# Index_Registers_-_1_0.net
KiCad netlist of a schematic drawn in EAGLE
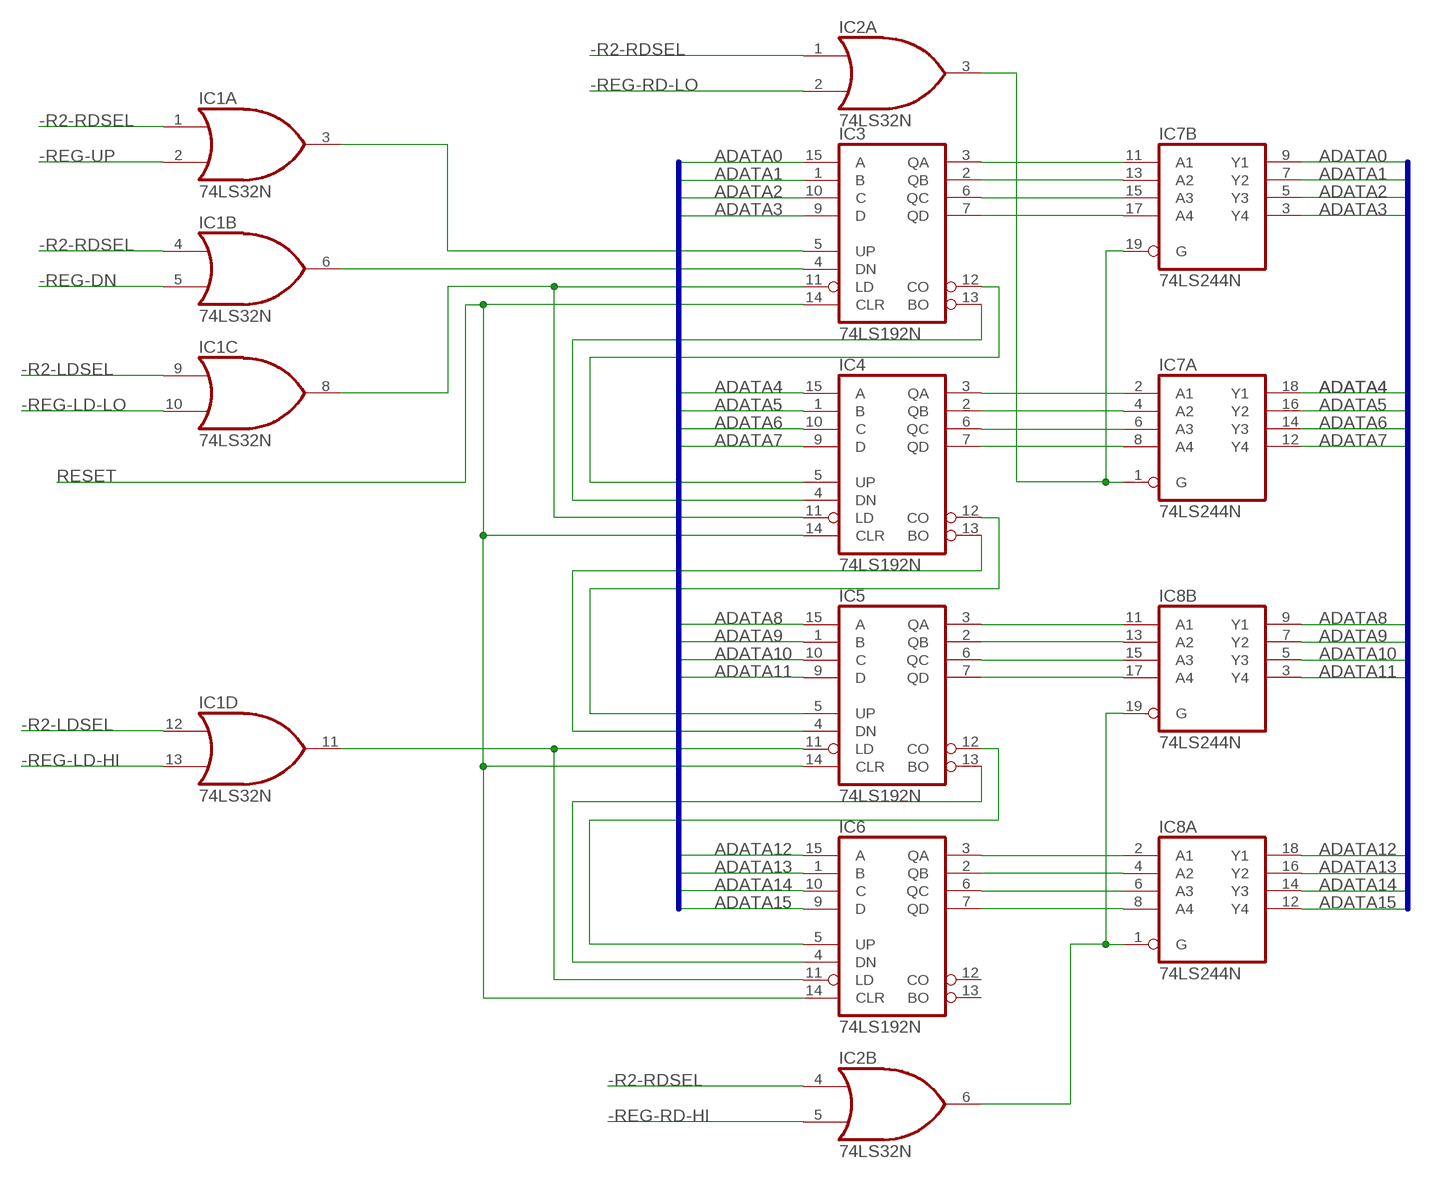
[diagram p0: schematic, sheet 1]
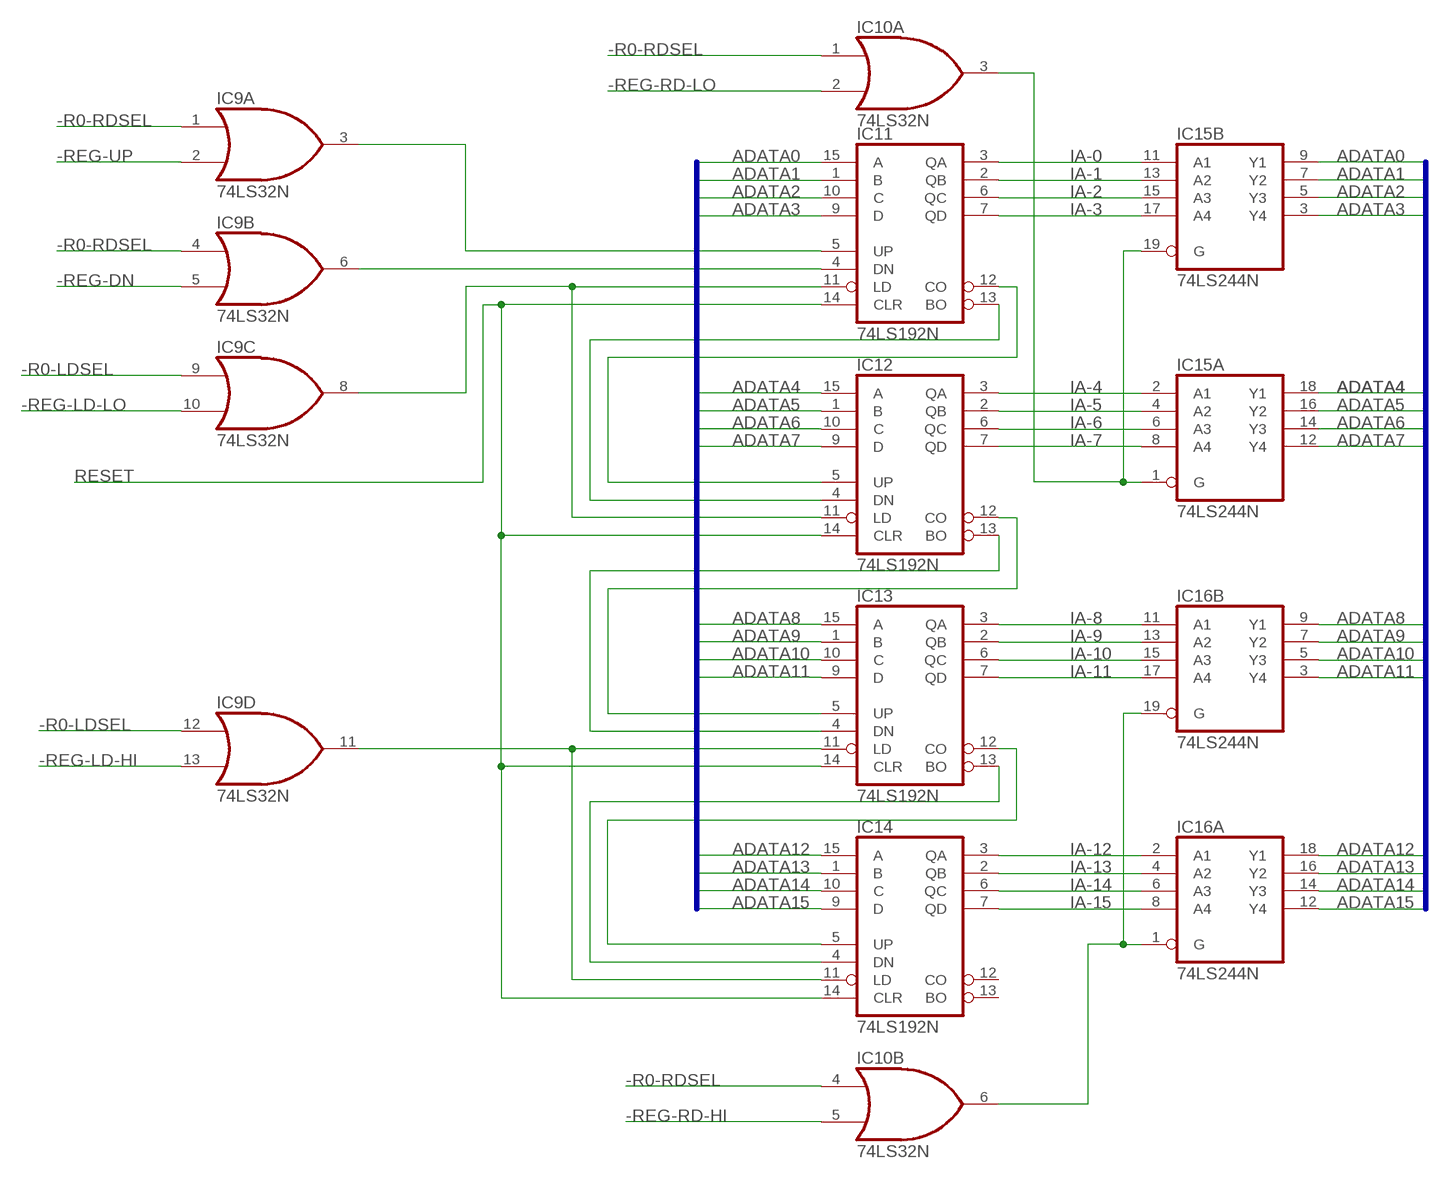
[diagram p1: schematic, sheet 2]
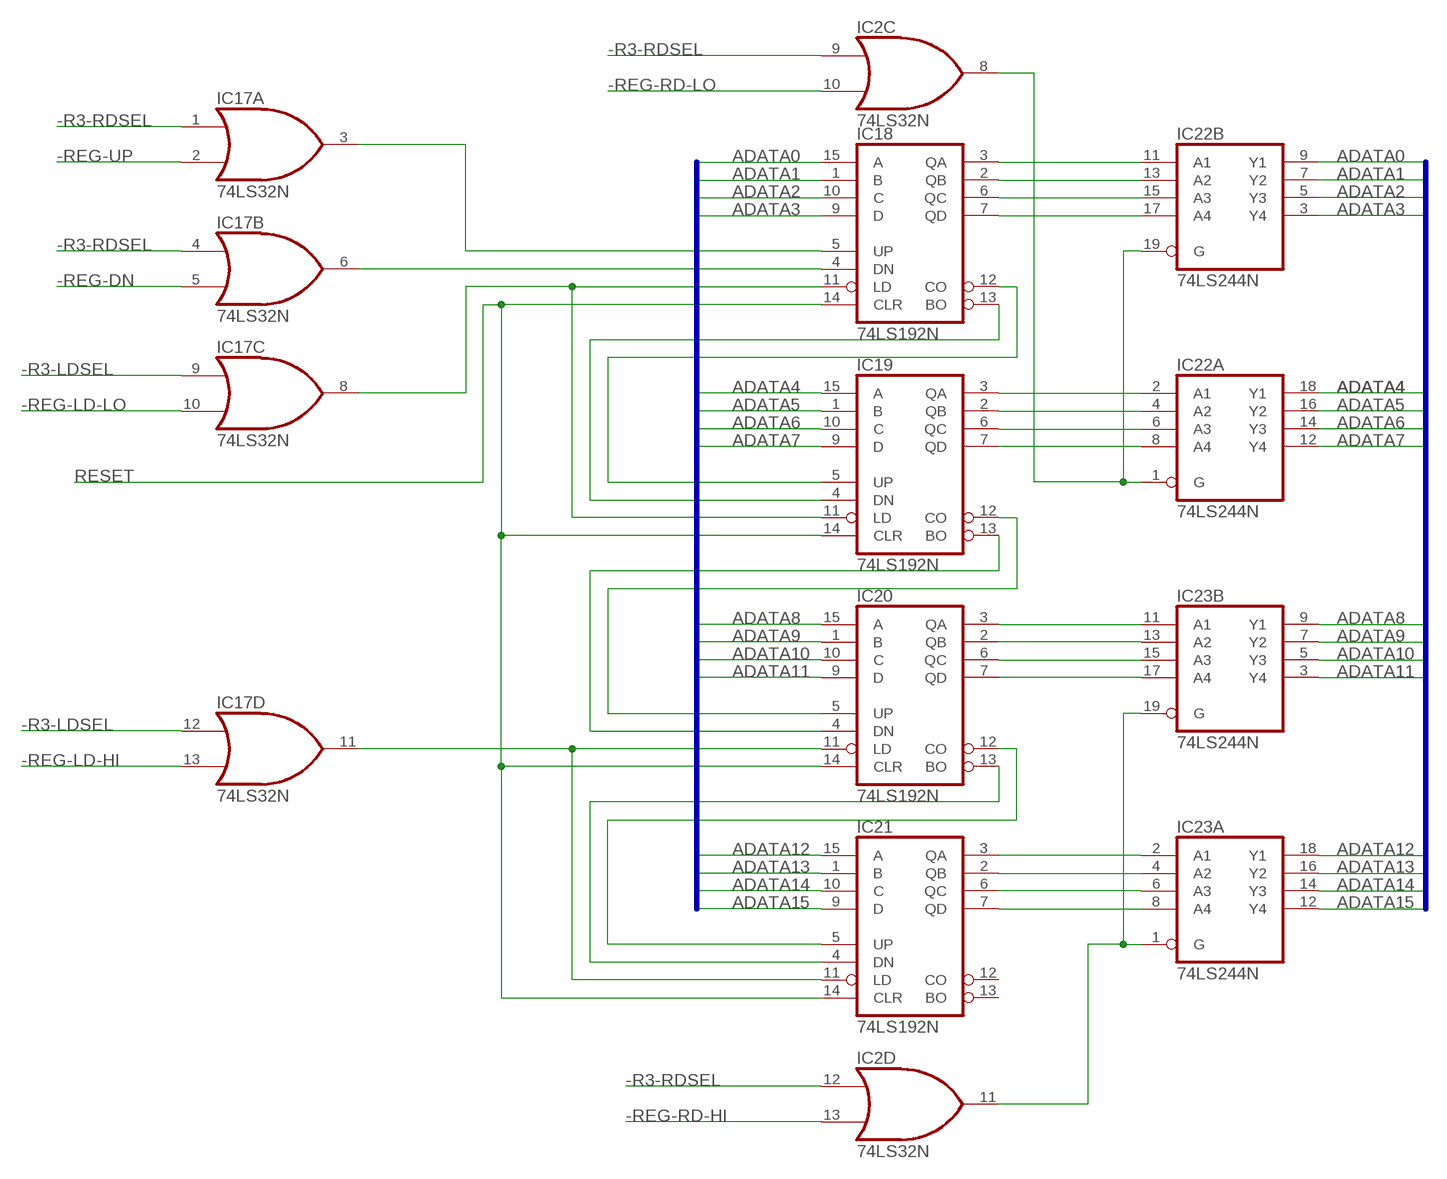
[diagram p2: schematic, sheet 3]
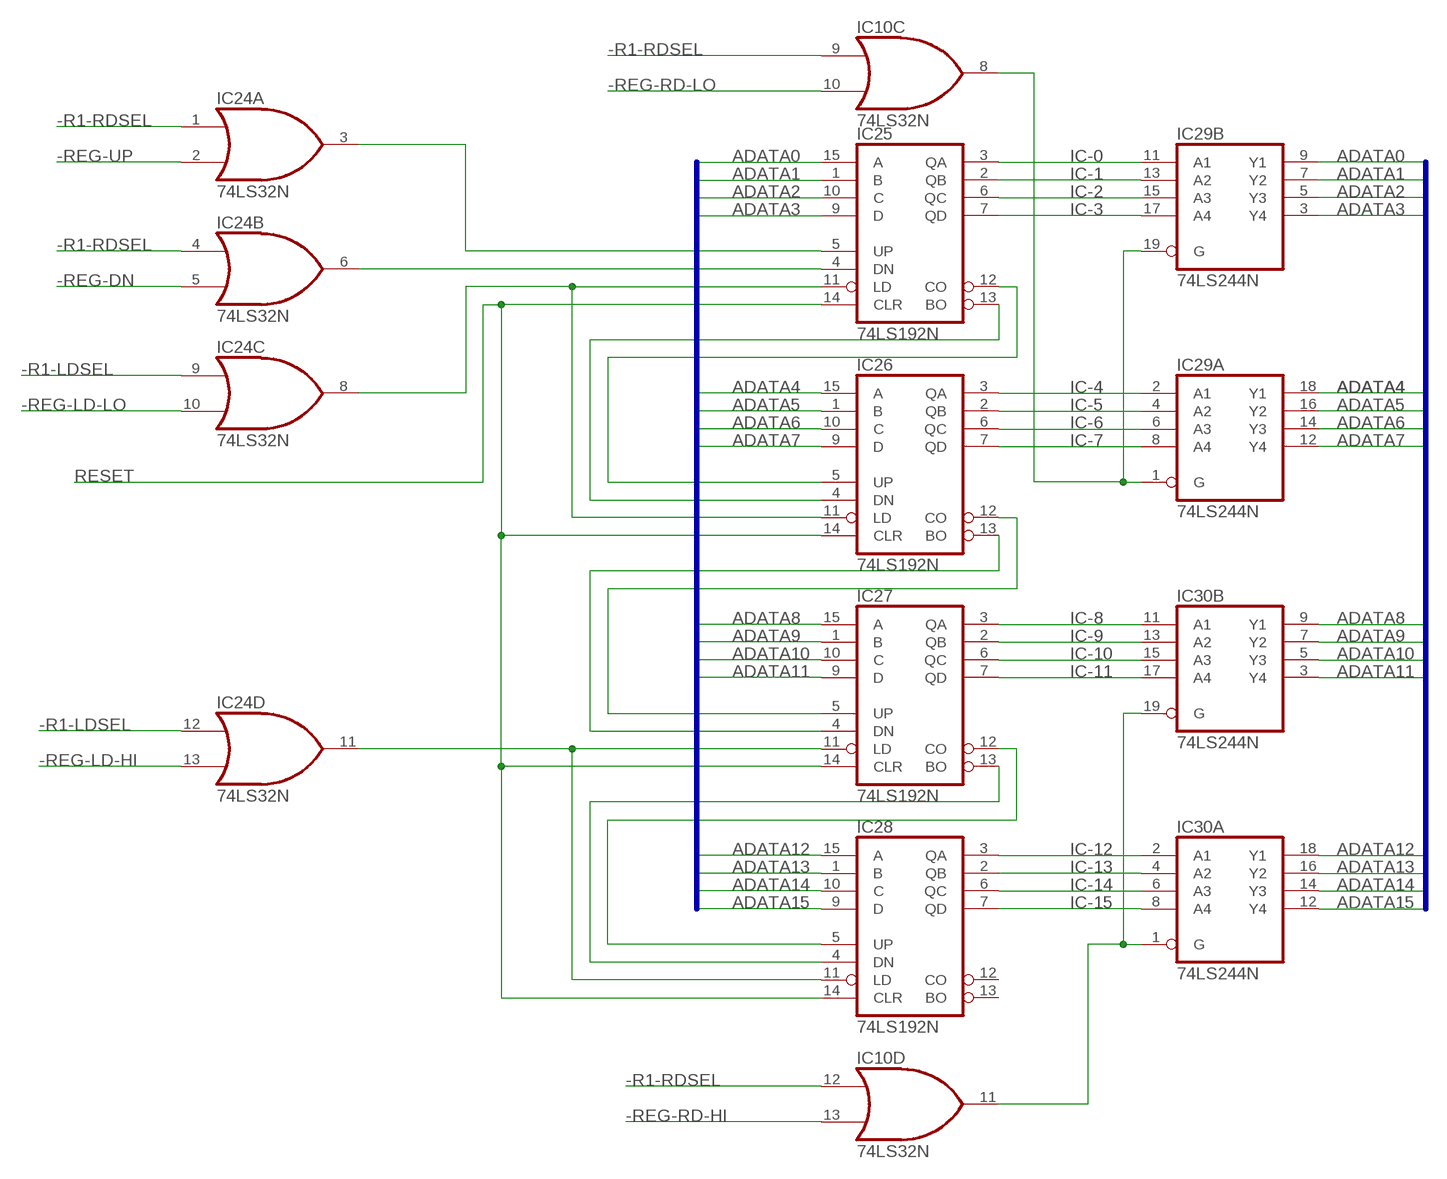
[diagram p3: schematic, sheet 4]
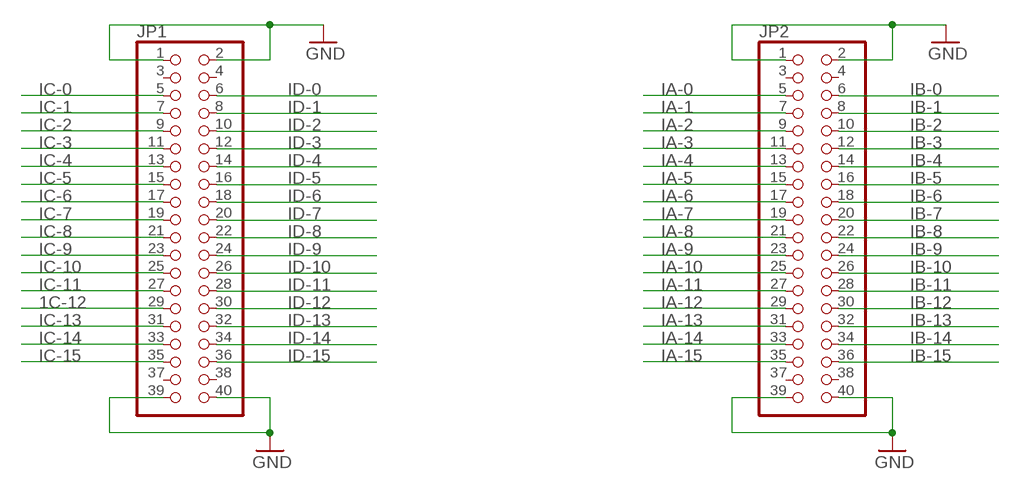
[diagram p4: schematic, sheet 5]
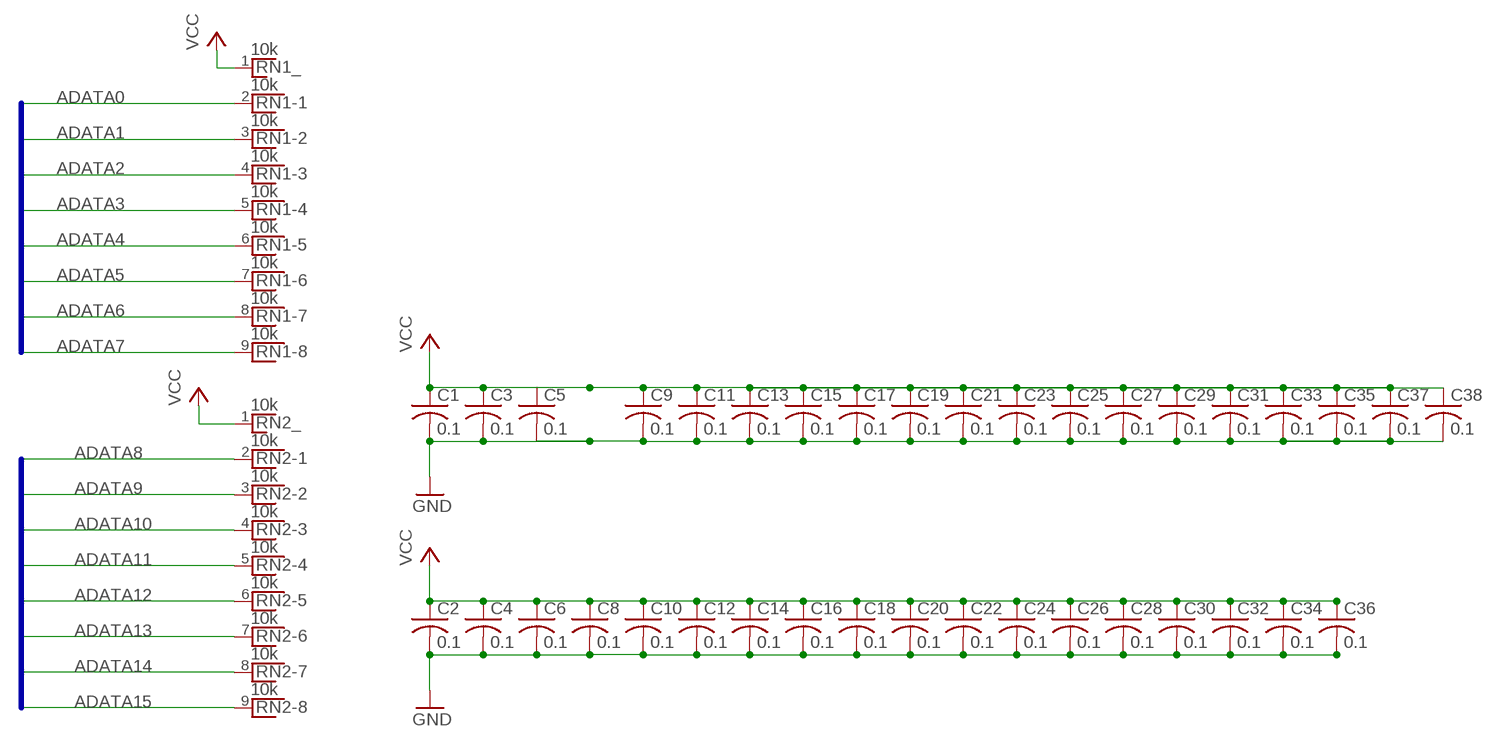
[diagram p5: schematic, sheet 6]
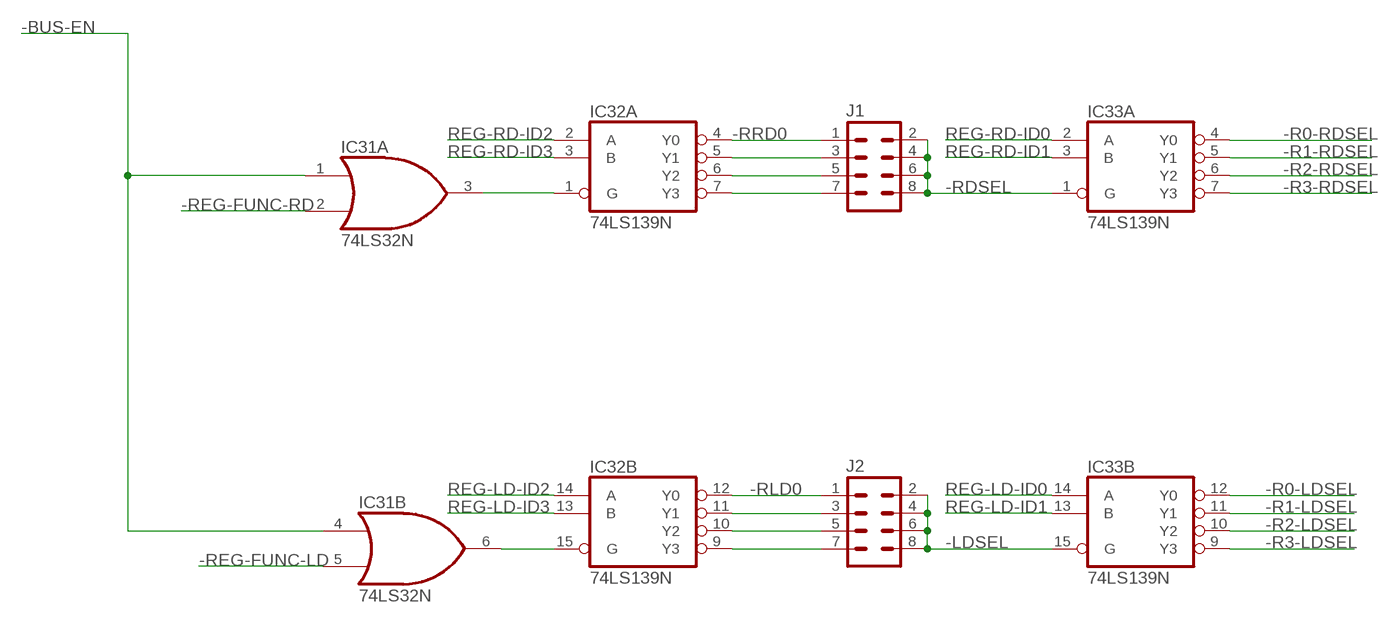
[diagram p6: schematic, sheet 7]
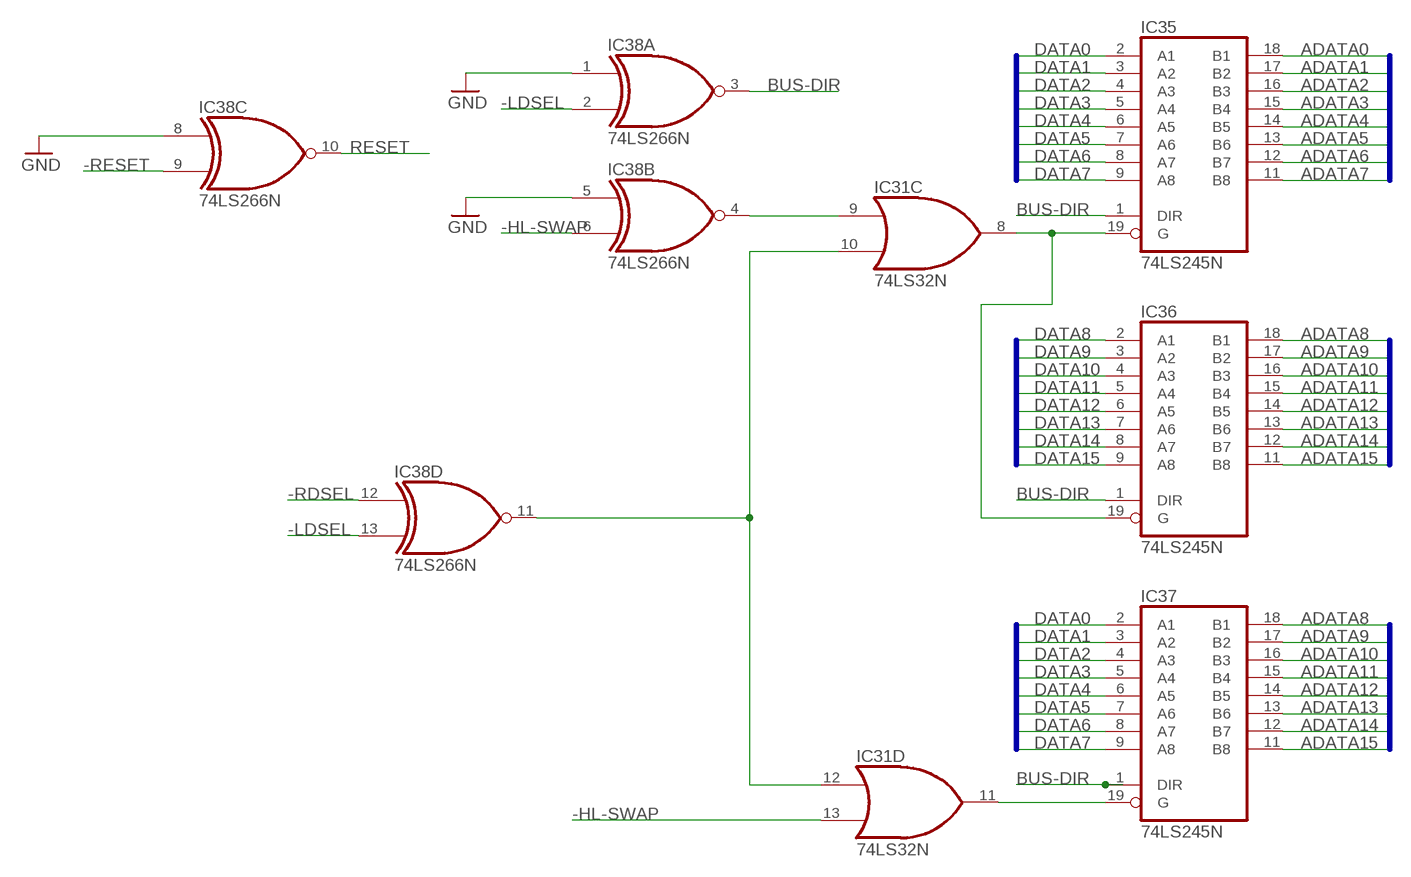
[diagram p7: schematic, sheet 8]
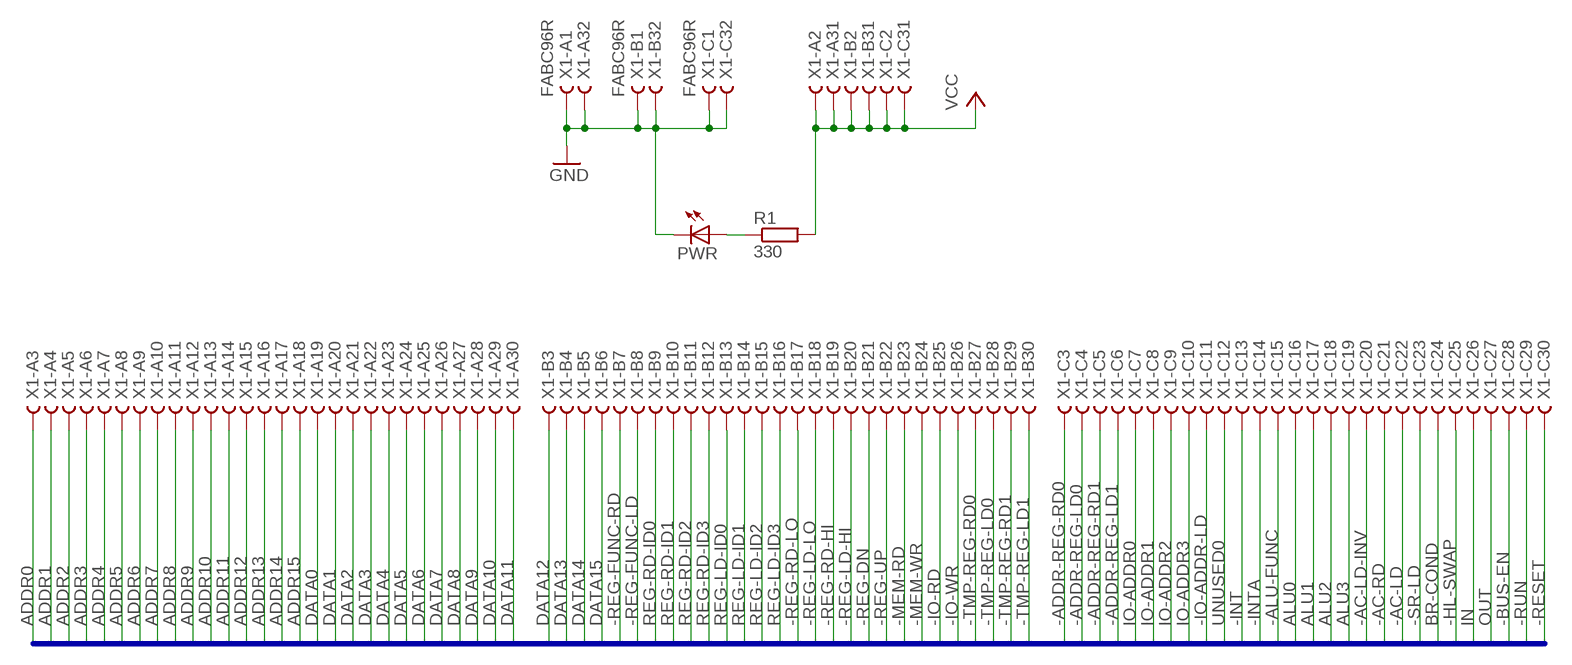
[diagram p8: schematic, sheet 9]

(export (version "E")
  (design (tool "Eeschema 10.0.6"))
  (components
    (comp (ref "IC31")
      (value "74LS32N")
      (footprint "eagle-import:DIL14")
      (libsource (lib "eagle-import") (part "7432NLS"))
    )
    (comp (ref "IC32")
      (value "74LS139N")
      (footprint "eagle-import:DIL16")
      (libsource (lib "eagle-import") (part "74139NLS"))
    )
    (comp (ref "IC33")
      (value "74LS139N")
      (footprint "eagle-import:DIL16")
      (libsource (lib "eagle-import") (part "74139NLS"))
    )
    (comp (ref "J1")
      (value "M04X2")
      (footprint "eagle-import:2X4")
      (libsource (lib "eagle-import") (part "M04X2"))
    )
    (comp (ref "J2")
      (value "M04X2")
      (footprint "eagle-import:2X4")
      (libsource (lib "eagle-import") (part "M04X2"))
    )
    (comp (ref "C1")
      (value "0.1")
      (footprint "eagle-import:C025-040X050")
      (libsource (lib "eagle-import") (part "C-US025-040X050"))
    )
    (comp (ref "C2")
      (value "0.1")
      (footprint "eagle-import:C025-040X050")
      (libsource (lib "eagle-import") (part "C-US025-040X050"))
    )
    (comp (ref "C3")
      (value "0.1")
      (footprint "eagle-import:C025-040X050")
      (libsource (lib "eagle-import") (part "C-US025-040X050"))
    )
    (comp (ref "C4")
      (value "0.1")
      (footprint "eagle-import:C025-040X050")
      (libsource (lib "eagle-import") (part "C-US025-040X050"))
    )
    (comp (ref "C5")
      (value "0.1")
      (footprint "eagle-import:C025-040X050")
      (libsource (lib "eagle-import") (part "C-US025-040X050"))
    )
    (comp (ref "C6")
      (value "0.1")
      (footprint "eagle-import:C025-040X050")
      (libsource (lib "eagle-import") (part "C-US025-040X050"))
    )
    (comp (ref "C8")
      (value "0.1")
      (footprint "eagle-import:C025-040X050")
      (libsource (lib "eagle-import") (part "C-US025-040X050"))
    )
    (comp (ref "C9")
      (value "0.1")
      (footprint "eagle-import:C025-040X050")
      (libsource (lib "eagle-import") (part "C-US025-040X050"))
    )
    (comp (ref "C10")
      (value "0.1")
      (footprint "eagle-import:C025-040X050")
      (libsource (lib "eagle-import") (part "C-US025-040X050"))
    )
    (comp (ref "C11")
      (value "0.1")
      (footprint "eagle-import:C025-040X050")
      (libsource (lib "eagle-import") (part "C-US025-040X050"))
    )
    (comp (ref "C12")
      (value "0.1")
      (footprint "eagle-import:C025-040X050")
      (libsource (lib "eagle-import") (part "C-US025-040X050"))
    )
    (comp (ref "C13")
      (value "0.1")
      (footprint "eagle-import:C025-040X050")
      (libsource (lib "eagle-import") (part "C-US025-040X050"))
    )
    (comp (ref "C14")
      (value "0.1")
      (footprint "eagle-import:C025-040X050")
      (libsource (lib "eagle-import") (part "C-US025-040X050"))
    )
    (comp (ref "C15")
      (value "0.1")
      (footprint "eagle-import:C025-040X050")
      (libsource (lib "eagle-import") (part "C-US025-040X050"))
    )
    (comp (ref "C16")
      (value "0.1")
      (footprint "eagle-import:C025-040X050")
      (libsource (lib "eagle-import") (part "C-US025-040X050"))
    )
    (comp (ref "C17")
      (value "0.1")
      (footprint "eagle-import:C025-040X050")
      (libsource (lib "eagle-import") (part "C-US025-040X050"))
    )
    (comp (ref "C18")
      (value "0.1")
      (footprint "eagle-import:C025-040X050")
      (libsource (lib "eagle-import") (part "C-US025-040X050"))
    )
    (comp (ref "C19")
      (value "0.1")
      (footprint "eagle-import:C025-040X050")
      (libsource (lib "eagle-import") (part "C-US025-040X050"))
    )
    (comp (ref "C20")
      (value "0.1")
      (footprint "eagle-import:C025-040X050")
      (libsource (lib "eagle-import") (part "C-US025-040X050"))
    )
    (comp (ref "C21")
      (value "0.1")
      (footprint "eagle-import:C025-040X050")
      (libsource (lib "eagle-import") (part "C-US025-040X050"))
    )
    (comp (ref "C22")
      (value "0.1")
      (footprint "eagle-import:C025-040X050")
      (libsource (lib "eagle-import") (part "C-US025-040X050"))
    )
    (comp (ref "C23")
      (value "0.1")
      (footprint "eagle-import:C025-040X050")
      (libsource (lib "eagle-import") (part "C-US025-040X050"))
    )
    (comp (ref "C24")
      (value "0.1")
      (footprint "eagle-import:C025-040X050")
      (libsource (lib "eagle-import") (part "C-US025-040X050"))
    )
    (comp (ref "C25")
      (value "0.1")
      (footprint "eagle-import:C025-040X050")
      (libsource (lib "eagle-import") (part "C-US025-040X050"))
    )
    (comp (ref "C26")
      (value "0.1")
      (footprint "eagle-import:C025-040X050")
      (libsource (lib "eagle-import") (part "C-US025-040X050"))
    )
    (comp (ref "C27")
      (value "0.1")
      (footprint "eagle-import:C025-040X050")
      (libsource (lib "eagle-import") (part "C-US025-040X050"))
    )
    (comp (ref "C28")
      (value "0.1")
      (footprint "eagle-import:C025-040X050")
      (libsource (lib "eagle-import") (part "C-US025-040X050"))
    )
    (comp (ref "C29")
      (value "0.1")
      (footprint "eagle-import:C025-040X050")
      (libsource (lib "eagle-import") (part "C-US025-040X050"))
    )
    (comp (ref "C30")
      (value "0.1")
      (footprint "eagle-import:C025-040X050")
      (libsource (lib "eagle-import") (part "C-US025-040X050"))
    )
    (comp (ref "C31")
      (value "0.1")
      (footprint "eagle-import:C025-040X050")
      (libsource (lib "eagle-import") (part "C-US025-040X050"))
    )
    (comp (ref "C32")
      (value "0.1")
      (footprint "eagle-import:C025-040X050")
      (libsource (lib "eagle-import") (part "C-US025-040X050"))
    )
    (comp (ref "C33")
      (value "0.1")
      (footprint "eagle-import:C025-040X050")
      (libsource (lib "eagle-import") (part "C-US025-040X050"))
    )
    (comp (ref "C34")
      (value "0.1")
      (footprint "eagle-import:C025-040X050")
      (libsource (lib "eagle-import") (part "C-US025-040X050"))
    )
    (comp (ref "C35")
      (value "0.1")
      (footprint "eagle-import:C025-040X050")
      (libsource (lib "eagle-import") (part "C-US025-040X050"))
    )
    (comp (ref "C36")
      (value "0.1")
      (footprint "eagle-import:C025-040X050")
      (libsource (lib "eagle-import") (part "C-US025-040X050"))
    )
    (comp (ref "C37")
      (value "0.1")
      (footprint "eagle-import:C025-040X050")
      (libsource (lib "eagle-import") (part "C-US025-040X050"))
    )
    (comp (ref "C38")
      (value "0.1")
      (footprint "eagle-import:C025-040X050")
      (libsource (lib "eagle-import") (part "C-US025-040X050"))
    )
    (comp (ref "RN1")
      (value "10k")
      (footprint "eagle-import:RN-9")
      (libsource (lib "eagle-import") (part "RNX8"))
    )
    (comp (ref "RN2")
      (value "10k")
      (footprint "eagle-import:RN-9")
      (libsource (lib "eagle-import") (part "RNX8"))
    )
    (comp (ref "IC1")
      (value "74LS32N")
      (footprint "eagle-import:DIL14")
      (libsource (lib "eagle-import") (part "7432NLS"))
    )
    (comp (ref "IC2")
      (value "74LS32N")
      (footprint "eagle-import:DIL14")
      (libsource (lib "eagle-import") (part "7432NLS"))
    )
    (comp (ref "IC3")
      (value "74LS192N")
      (footprint "eagle-import:DIL16")
      (libsource (lib "eagle-import") (part "74192NLS"))
    )
    (comp (ref "IC4")
      (value "74LS192N")
      (footprint "eagle-import:DIL16")
      (libsource (lib "eagle-import") (part "74192NLS"))
    )
    (comp (ref "IC5")
      (value "74LS192N")
      (footprint "eagle-import:DIL16")
      (libsource (lib "eagle-import") (part "74192NLS"))
    )
    (comp (ref "IC6")
      (value "74LS192N")
      (footprint "eagle-import:DIL16")
      (libsource (lib "eagle-import") (part "74192NLS"))
    )
    (comp (ref "IC7")
      (value "74LS244N")
      (footprint "eagle-import:DIL20")
      (libsource (lib "eagle-import") (part "74xx-us_74244NLS"))
    )
    (comp (ref "IC8")
      (value "74LS244N")
      (footprint "eagle-import:DIL20")
      (libsource (lib "eagle-import") (part "74xx-us_74244NLS"))
    )
    (comp (ref "IC17")
      (value "74LS32N")
      (footprint "eagle-import:DIL14")
      (libsource (lib "eagle-import") (part "7432NLS"))
    )
    (comp (ref "IC18")
      (value "74LS192N")
      (footprint "eagle-import:DIL16")
      (libsource (lib "eagle-import") (part "74192NLS"))
    )
    (comp (ref "IC19")
      (value "74LS192N")
      (footprint "eagle-import:DIL16")
      (libsource (lib "eagle-import") (part "74192NLS"))
    )
    (comp (ref "IC20")
      (value "74LS192N")
      (footprint "eagle-import:DIL16")
      (libsource (lib "eagle-import") (part "74192NLS"))
    )
    (comp (ref "IC21")
      (value "74LS192N")
      (footprint "eagle-import:DIL16")
      (libsource (lib "eagle-import") (part "74192NLS"))
    )
    (comp (ref "IC22")
      (value "74LS244N")
      (footprint "eagle-import:DIL20")
      (libsource (lib "eagle-import") (part "74xx-us_74244NLS"))
    )
    (comp (ref "IC23")
      (value "74LS244N")
      (footprint "eagle-import:DIL20")
      (libsource (lib "eagle-import") (part "74xx-us_74244NLS"))
    )
    (comp (ref "IC10")
      (value "74LS32N")
      (footprint "eagle-import:DIL14")
      (libsource (lib "eagle-import") (part "7432NLS"))
    )
    (comp (ref "IC24")
      (value "74LS32N")
      (footprint "eagle-import:DIL14")
      (libsource (lib "eagle-import") (part "7432NLS"))
    )
    (comp (ref "IC25")
      (value "74LS192N")
      (footprint "eagle-import:DIL16")
      (libsource (lib "eagle-import") (part "74192NLS"))
    )
    (comp (ref "IC26")
      (value "74LS192N")
      (footprint "eagle-import:DIL16")
      (libsource (lib "eagle-import") (part "74192NLS"))
    )
    (comp (ref "IC27")
      (value "74LS192N")
      (footprint "eagle-import:DIL16")
      (libsource (lib "eagle-import") (part "74192NLS"))
    )
    (comp (ref "IC28")
      (value "74LS192N")
      (footprint "eagle-import:DIL16")
      (libsource (lib "eagle-import") (part "74192NLS"))
    )
    (comp (ref "IC29")
      (value "74LS244N")
      (footprint "eagle-import:DIL20")
      (libsource (lib "eagle-import") (part "74xx-us_74244NLS"))
    )
    (comp (ref "IC30")
      (value "74LS244N")
      (footprint "eagle-import:DIL20")
      (libsource (lib "eagle-import") (part "74xx-us_74244NLS"))
    )
    (comp (ref "PWR")
      (value "LED5MM")
      (footprint "eagle-import:LED5MM")
      (libsource (lib "eagle-import") (part "LED5MM"))
    )
    (comp (ref "R1")
      (value "330")
      (footprint "eagle-import:0207_10")
      (libsource (lib "eagle-import") (part "R0207/10"))
    )
    (comp (ref "X1")
      (value "FABC96R")
      (footprint "eagle-import:FABC96R")
      (libsource (lib "eagle-import") (part "FABC96R"))
    )
    (comp (ref "JP1")
      (value "PINHD-2X20")
      (footprint "eagle-import:2X20")
      (libsource (lib "eagle-import") (part "PINHD-2X20"))
    )
    (comp (ref "JP2")
      (value "PINHD-2X20")
      (footprint "eagle-import:2X20")
      (libsource (lib "eagle-import") (part "PINHD-2X20"))
    )
    (comp (ref "IC9")
      (value "74LS32N")
      (footprint "eagle-import:DIL14")
      (libsource (lib "eagle-import") (part "7432NLS"))
    )
    (comp (ref "IC11")
      (value "74LS192N")
      (footprint "eagle-import:DIL16")
      (libsource (lib "eagle-import") (part "74192NLS"))
    )
    (comp (ref "IC12")
      (value "74LS192N")
      (footprint "eagle-import:DIL16")
      (libsource (lib "eagle-import") (part "74192NLS"))
    )
    (comp (ref "IC13")
      (value "74LS192N")
      (footprint "eagle-import:DIL16")
      (libsource (lib "eagle-import") (part "74192NLS"))
    )
    (comp (ref "IC14")
      (value "74LS192N")
      (footprint "eagle-import:DIL16")
      (libsource (lib "eagle-import") (part "74192NLS"))
    )
    (comp (ref "IC15")
      (value "74LS244N")
      (footprint "eagle-import:DIL20")
      (libsource (lib "eagle-import") (part "74xx-us_74244NLS"))
    )
    (comp (ref "IC16")
      (value "74LS244N")
      (footprint "eagle-import:DIL20")
      (libsource (lib "eagle-import") (part "74xx-us_74244NLS"))
    )
    (comp (ref "IC35")
      (value "74LS245N")
      (footprint "eagle-import:DIL20")
      (libsource (lib "eagle-import") (part "74245NLS"))
    )
    (comp (ref "IC36")
      (value "74LS245N")
      (footprint "eagle-import:DIL20")
      (libsource (lib "eagle-import") (part "74245NLS"))
    )
    (comp (ref "IC37")
      (value "74LS245N")
      (footprint "eagle-import:DIL20")
      (libsource (lib "eagle-import") (part "74245NLS"))
    )
    (comp (ref "IC38")
      (value "74LS266N")
      (footprint "eagle-import:DIL14")
      (libsource (lib "eagle-import") (part "74266NLS"))
    )
  )
  (nets
    (net (code "1") (name "-AC-LD") (class "Default")
      (node (ref "X1") (pin "C22") (pinfunction "B_C22") (pintype "passive"))
    )
    (net (code "2") (name "-AC-LD-INV") (class "Default")
      (node (ref "X1") (pin "C20") (pinfunction "B_C20") (pintype "passive"))
    )
    (net (code "3") (name "-AC-RD") (class "Default")
      (node (ref "X1") (pin "C21") (pinfunction "B_C21") (pintype "passive"))
    )
    (net (code "4") (name "-ADDR-REG-LD0") (class "Default")
      (node (ref "X1") (pin "C4") (pinfunction "B_C4") (pintype "passive"))
    )
    (net (code "5") (name "-ADDR-REG-LD1") (class "Default")
      (node (ref "X1") (pin "C6") (pinfunction "B_C6") (pintype "passive"))
    )
    (net (code "6") (name "-ADDR-REG-RD0") (class "Default")
      (node (ref "X1") (pin "C3") (pinfunction "B_C3") (pintype "passive"))
    )
    (net (code "7") (name "-ADDR-REG-RD1") (class "Default")
      (node (ref "X1") (pin "C5") (pinfunction "B_C5") (pintype "passive"))
    )
    (net (code "8") (name "-ALU-FUNC") (class "Default")
      (node (ref "X1") (pin "C15") (pinfunction "B_C15") (pintype "passive"))
    )
    (net (code "9") (name "-BUS-EN") (class "Default")
      (node (ref "IC31") (pin "1") (pinfunction "I0_1") (pintype "input"))
      (node (ref "IC31") (pin "4") (pinfunction "I0_4") (pintype "input"))
      (node (ref "X1") (pin "C28") (pinfunction "B_C28") (pintype "passive"))
    )
    (net (code "10") (name "-HL-SWAP") (class "Default")
      (node (ref "IC31") (pin "13") (pinfunction "I1_13") (pintype "input"))
      (node (ref "IC38") (pin "6") (pinfunction "I1_6") (pintype "input"))
      (node (ref "X1") (pin "C25") (pinfunction "B_C25") (pintype "passive"))
    )
    (net (code "11") (name "-INT") (class "Default")
      (node (ref "X1") (pin "C13") (pinfunction "B_C13") (pintype "passive"))
    )
    (net (code "12") (name "-INTA") (class "Default")
      (node (ref "X1") (pin "C14") (pinfunction "B_C14") (pintype "passive"))
    )
    (net (code "13") (name "-IO-ADDR-LD") (class "Default")
      (node (ref "X1") (pin "C11") (pinfunction "B_C11") (pintype "passive"))
    )
    (net (code "14") (name "-IO-RD") (class "Default")
      (node (ref "X1") (pin "B25") (pinfunction "B_B25") (pintype "passive"))
    )
    (net (code "15") (name "-IO-WR") (class "Default")
      (node (ref "X1") (pin "B26") (pinfunction "B_B26") (pintype "passive"))
    )
    (net (code "16") (name "-LDSEL") (class "Default")
      (node (ref "IC33") (pin "15") (pinfunction "G_15") (pintype "input"))
      (node (ref "IC38") (pin "13") (pinfunction "I1_13") (pintype "input"))
      (node (ref "IC38") (pin "2") (pinfunction "I1_2") (pintype "input"))
      (node (ref "J2") (pin "2") (pinfunction "2_2") (pintype "passive"))
      (node (ref "J2") (pin "4") (pinfunction "4_4") (pintype "passive"))
      (node (ref "J2") (pin "6") (pinfunction "6_6") (pintype "passive"))
      (node (ref "J2") (pin "8") (pinfunction "8_8") (pintype "passive"))
    )
    (net (code "17") (name "-MEM-RD") (class "Default")
      (node (ref "X1") (pin "B23") (pinfunction "B_B23") (pintype "passive"))
    )
    (net (code "18") (name "-MEM-WR") (class "Default")
      (node (ref "X1") (pin "B24") (pinfunction "B_B24") (pintype "passive"))
    )
    (net (code "19") (name "-R0-LDSEL") (class "Default")
      (node (ref "IC33") (pin "12") (pinfunction "Y0_12") (pintype "output"))
      (node (ref "IC9") (pin "12") (pinfunction "I0_12") (pintype "input"))
      (node (ref "IC9") (pin "9") (pinfunction "I0_9") (pintype "input"))
    )
    (net (code "20") (name "-R0-RDSEL") (class "Default")
      (node (ref "IC10") (pin "1") (pinfunction "I0_1") (pintype "input"))
      (node (ref "IC10") (pin "4") (pinfunction "I0_4") (pintype "input"))
      (node (ref "IC33") (pin "4") (pinfunction "Y0_4") (pintype "output"))
      (node (ref "IC9") (pin "1") (pinfunction "I0_1") (pintype "input"))
      (node (ref "IC9") (pin "4") (pinfunction "I0_4") (pintype "input"))
    )
    (net (code "21") (name "-R1-LDSEL") (class "Default")
      (node (ref "IC24") (pin "12") (pinfunction "I0_12") (pintype "input"))
      (node (ref "IC24") (pin "9") (pinfunction "I0_9") (pintype "input"))
      (node (ref "IC33") (pin "11") (pinfunction "Y1_11") (pintype "output"))
    )
    (net (code "22") (name "-R1-RDSEL") (class "Default")
      (node (ref "IC10") (pin "12") (pinfunction "I0_12") (pintype "input"))
      (node (ref "IC10") (pin "9") (pinfunction "I0_9") (pintype "input"))
      (node (ref "IC24") (pin "1") (pinfunction "I0_1") (pintype "input"))
      (node (ref "IC24") (pin "4") (pinfunction "I0_4") (pintype "input"))
      (node (ref "IC33") (pin "5") (pinfunction "Y1_5") (pintype "output"))
    )
    (net (code "23") (name "-R2-LDSEL") (class "Default")
      (node (ref "IC1") (pin "12") (pinfunction "I0_12") (pintype "input"))
      (node (ref "IC1") (pin "9") (pinfunction "I0_9") (pintype "input"))
      (node (ref "IC33") (pin "10") (pinfunction "Y2_10") (pintype "output"))
    )
    (net (code "24") (name "-R2-RDSEL") (class "Default")
      (node (ref "IC1") (pin "1") (pinfunction "I0_1") (pintype "input"))
      (node (ref "IC1") (pin "4") (pinfunction "I0_4") (pintype "input"))
      (node (ref "IC2") (pin "1") (pinfunction "I0_1") (pintype "input"))
      (node (ref "IC2") (pin "4") (pinfunction "I0_4") (pintype "input"))
      (node (ref "IC33") (pin "6") (pinfunction "Y2_6") (pintype "output"))
    )
    (net (code "25") (name "-R3-LDSEL") (class "Default")
      (node (ref "IC17") (pin "12") (pinfunction "I0_12") (pintype "input"))
      (node (ref "IC17") (pin "9") (pinfunction "I0_9") (pintype "input"))
      (node (ref "IC33") (pin "9") (pinfunction "Y3_9") (pintype "output"))
    )
    (net (code "26") (name "-R3-RDSEL") (class "Default")
      (node (ref "IC17") (pin "1") (pinfunction "I0_1") (pintype "input"))
      (node (ref "IC17") (pin "4") (pinfunction "I0_4") (pintype "input"))
      (node (ref "IC2") (pin "12") (pinfunction "I0_12") (pintype "input"))
      (node (ref "IC2") (pin "9") (pinfunction "I0_9") (pintype "input"))
      (node (ref "IC33") (pin "7") (pinfunction "Y3_7") (pintype "output"))
    )
    (net (code "27") (name "-RDSEL") (class "Default")
      (node (ref "IC33") (pin "1") (pinfunction "G_1") (pintype "input"))
      (node (ref "IC38") (pin "12") (pinfunction "I0_12") (pintype "input"))
      (node (ref "J1") (pin "2") (pinfunction "2_2") (pintype "passive"))
      (node (ref "J1") (pin "4") (pinfunction "4_4") (pintype "passive"))
      (node (ref "J1") (pin "6") (pinfunction "6_6") (pintype "passive"))
      (node (ref "J1") (pin "8") (pinfunction "8_8") (pintype "passive"))
    )
    (net (code "28") (name "-REG-DN") (class "Default")
      (node (ref "IC1") (pin "5") (pinfunction "I1_5") (pintype "input"))
      (node (ref "IC17") (pin "5") (pinfunction "I1_5") (pintype "input"))
      (node (ref "IC24") (pin "5") (pinfunction "I1_5") (pintype "input"))
      (node (ref "IC9") (pin "5") (pinfunction "I1_5") (pintype "input"))
      (node (ref "X1") (pin "B21") (pinfunction "B_B21") (pintype "passive"))
    )
    (net (code "29") (name "-REG-FUNC-LD") (class "Default")
      (node (ref "IC31") (pin "5") (pinfunction "I1_5") (pintype "input"))
      (node (ref "X1") (pin "B8") (pinfunction "B_B8") (pintype "passive"))
    )
    (net (code "30") (name "-REG-FUNC-RD") (class "Default")
      (node (ref "IC31") (pin "2") (pinfunction "I1_2") (pintype "input"))
      (node (ref "X1") (pin "B7") (pinfunction "B_B7") (pintype "passive"))
    )
    (net (code "31") (name "-REG-LD-HI") (class "Default")
      (node (ref "IC1") (pin "13") (pinfunction "I1_13") (pintype "input"))
      (node (ref "IC17") (pin "13") (pinfunction "I1_13") (pintype "input"))
      (node (ref "IC24") (pin "13") (pinfunction "I1_13") (pintype "input"))
      (node (ref "IC9") (pin "13") (pinfunction "I1_13") (pintype "input"))
      (node (ref "X1") (pin "B20") (pinfunction "B_B20") (pintype "passive"))
    )
    (net (code "32") (name "-REG-LD-LO") (class "Default")
      (node (ref "IC1") (pin "10") (pinfunction "I1_10") (pintype "input"))
      (node (ref "IC17") (pin "10") (pinfunction "I1_10") (pintype "input"))
      (node (ref "IC24") (pin "10") (pinfunction "I1_10") (pintype "input"))
      (node (ref "IC9") (pin "10") (pinfunction "I1_10") (pintype "input"))
      (node (ref "X1") (pin "B18") (pinfunction "B_B18") (pintype "passive"))
    )
    (net (code "33") (name "-REG-RD-HI") (class "Default")
      (node (ref "IC10") (pin "13") (pinfunction "I1_13") (pintype "input"))
      (node (ref "IC10") (pin "5") (pinfunction "I1_5") (pintype "input"))
      (node (ref "IC2") (pin "13") (pinfunction "I1_13") (pintype "input"))
      (node (ref "IC2") (pin "5") (pinfunction "I1_5") (pintype "input"))
      (node (ref "X1") (pin "B19") (pinfunction "B_B19") (pintype "passive"))
    )
    (net (code "34") (name "-REG-RD-LO") (class "Default")
      (node (ref "IC10") (pin "10") (pinfunction "I1_10") (pintype "input"))
      (node (ref "IC10") (pin "2") (pinfunction "I1_2") (pintype "input"))
      (node (ref "IC2") (pin "10") (pinfunction "I1_10") (pintype "input"))
      (node (ref "IC2") (pin "2") (pinfunction "I1_2") (pintype "input"))
      (node (ref "X1") (pin "B17") (pinfunction "B_B17") (pintype "passive"))
    )
    (net (code "35") (name "-REG-UP") (class "Default")
      (node (ref "IC1") (pin "2") (pinfunction "I1_2") (pintype "input"))
      (node (ref "IC17") (pin "2") (pinfunction "I1_2") (pintype "input"))
      (node (ref "IC24") (pin "2") (pinfunction "I1_2") (pintype "input"))
      (node (ref "IC9") (pin "2") (pinfunction "I1_2") (pintype "input"))
      (node (ref "X1") (pin "B22") (pinfunction "B_B22") (pintype "passive"))
    )
    (net (code "36") (name "-RESET") (class "Default")
      (node (ref "IC38") (pin "9") (pinfunction "I1_9") (pintype "input"))
      (node (ref "X1") (pin "C30") (pinfunction "B_C30") (pintype "passive"))
    )
    (net (code "37") (name "-RLD0") (class "Default")
      (node (ref "IC32") (pin "12") (pinfunction "Y0_12") (pintype "output"))
      (node (ref "J2") (pin "1") (pinfunction "1_1") (pintype "passive"))
    )
    (net (code "38") (name "-RRD0") (class "Default")
      (node (ref "IC32") (pin "4") (pinfunction "Y0_4") (pintype "output"))
      (node (ref "J1") (pin "1") (pinfunction "1_1") (pintype "passive"))
    )
    (net (code "39") (name "-RUN") (class "Default")
      (node (ref "X1") (pin "C29") (pinfunction "B_C29") (pintype "passive"))
    )
    (net (code "40") (name "-SR-LD") (class "Default")
      (node (ref "X1") (pin "C23") (pinfunction "B_C23") (pintype "passive"))
    )
    (net (code "41") (name "-TMP-REG-LD0") (class "Default")
      (node (ref "X1") (pin "B28") (pinfunction "B_B28") (pintype "passive"))
    )
    (net (code "42") (name "-TMP-REG-LD1") (class "Default")
      (node (ref "X1") (pin "B30") (pinfunction "B_B30") (pintype "passive"))
    )
    (net (code "43") (name "-TMP-REG-RD0") (class "Default")
      (node (ref "X1") (pin "B27") (pinfunction "B_B27") (pintype "passive"))
    )
    (net (code "44") (name "-TMP-REG-RD1") (class "Default")
      (node (ref "X1") (pin "B29") (pinfunction "B_B29") (pintype "passive"))
    )
    (net (code "45") (name "1C-12") (class "Default")
      (node (ref "JP1") (pin "29") (pinfunction "29_29") (pintype "passive"))
    )
    (net (code "46") (name "ADATA0") (class "Default")
      (node (ref "IC11") (pin "15") (pinfunction "A_15") (pintype "input"))
      (node (ref "IC15") (pin "9") (pinfunction "Y1_9") (pintype "tri_state"))
      (node (ref "IC18") (pin "15") (pinfunction "A_15") (pintype "input"))
      (node (ref "IC22") (pin "9") (pinfunction "Y1_9") (pintype "tri_state"))
      (node (ref "IC25") (pin "15") (pinfunction "A_15") (pintype "input"))
      (node (ref "IC29") (pin "9") (pinfunction "Y1_9") (pintype "tri_state"))
      (node (ref "IC3") (pin "15") (pinfunction "A_15") (pintype "input"))
      (node (ref "IC35") (pin "18") (pinfunction "B1_18") (pintype "bidirectional"))
      (node (ref "IC7") (pin "9") (pinfunction "Y1_9") (pintype "tri_state"))
      (node (ref "RN1") (pin "2") (pinfunction "1_2") (pintype "passive"))
    )
    (net (code "47") (name "ADATA1") (class "Default")
      (node (ref "IC11") (pin "1") (pinfunction "B_1") (pintype "input"))
      (node (ref "IC15") (pin "7") (pinfunction "Y2_7") (pintype "tri_state"))
      (node (ref "IC18") (pin "1") (pinfunction "B_1") (pintype "input"))
      (node (ref "IC22") (pin "7") (pinfunction "Y2_7") (pintype "tri_state"))
      (node (ref "IC25") (pin "1") (pinfunction "B_1") (pintype "input"))
      (node (ref "IC29") (pin "7") (pinfunction "Y2_7") (pintype "tri_state"))
      (node (ref "IC3") (pin "1") (pinfunction "B_1") (pintype "input"))
      (node (ref "IC35") (pin "17") (pinfunction "B2_17") (pintype "bidirectional"))
      (node (ref "IC7") (pin "7") (pinfunction "Y2_7") (pintype "tri_state"))
      (node (ref "RN1") (pin "3") (pinfunction "1_3") (pintype "passive"))
    )
    (net (code "48") (name "ADATA2") (class "Default")
      (node (ref "IC11") (pin "10") (pinfunction "C_10") (pintype "input"))
      (node (ref "IC15") (pin "5") (pinfunction "Y3_5") (pintype "tri_state"))
      (node (ref "IC18") (pin "10") (pinfunction "C_10") (pintype "input"))
      (node (ref "IC22") (pin "5") (pinfunction "Y3_5") (pintype "tri_state"))
      (node (ref "IC25") (pin "10") (pinfunction "C_10") (pintype "input"))
      (node (ref "IC29") (pin "5") (pinfunction "Y3_5") (pintype "tri_state"))
      (node (ref "IC3") (pin "10") (pinfunction "C_10") (pintype "input"))
      (node (ref "IC35") (pin "16") (pinfunction "B3_16") (pintype "bidirectional"))
      (node (ref "IC7") (pin "5") (pinfunction "Y3_5") (pintype "tri_state"))
      (node (ref "RN1") (pin "4") (pinfunction "1_4") (pintype "passive"))
    )
    (net (code "49") (name "ADATA3") (class "Default")
      (node (ref "IC11") (pin "9") (pinfunction "D_9") (pintype "input"))
      (node (ref "IC15") (pin "3") (pinfunction "Y4_3") (pintype "tri_state"))
      (node (ref "IC18") (pin "9") (pinfunction "D_9") (pintype "input"))
      (node (ref "IC22") (pin "3") (pinfunction "Y4_3") (pintype "tri_state"))
      (node (ref "IC25") (pin "9") (pinfunction "D_9") (pintype "input"))
      (node (ref "IC29") (pin "3") (pinfunction "Y4_3") (pintype "tri_state"))
      (node (ref "IC3") (pin "9") (pinfunction "D_9") (pintype "input"))
      (node (ref "IC35") (pin "15") (pinfunction "B4_15") (pintype "bidirectional"))
      (node (ref "IC7") (pin "3") (pinfunction "Y4_3") (pintype "tri_state"))
      (node (ref "RN1") (pin "5") (pinfunction "1_5") (pintype "passive"))
    )
    (net (code "50") (name "ADATA4") (class "Default")
      (node (ref "IC12") (pin "15") (pinfunction "A_15") (pintype "input"))
      (node (ref "IC15") (pin "18") (pinfunction "Y1_18") (pintype "tri_state"))
      (node (ref "IC19") (pin "15") (pinfunction "A_15") (pintype "input"))
      (node (ref "IC22") (pin "18") (pinfunction "Y1_18") (pintype "tri_state"))
      (node (ref "IC26") (pin "15") (pinfunction "A_15") (pintype "input"))
      (node (ref "IC29") (pin "18") (pinfunction "Y1_18") (pintype "tri_state"))
      (node (ref "IC35") (pin "14") (pinfunction "B5_14") (pintype "bidirectional"))
      (node (ref "IC4") (pin "15") (pinfunction "A_15") (pintype "input"))
      (node (ref "IC7") (pin "18") (pinfunction "Y1_18") (pintype "tri_state"))
      (node (ref "RN1") (pin "6") (pinfunction "1_6") (pintype "passive"))
    )
    (net (code "51") (name "ADATA5") (class "Default")
      (node (ref "IC12") (pin "1") (pinfunction "B_1") (pintype "input"))
      (node (ref "IC15") (pin "16") (pinfunction "Y2_16") (pintype "tri_state"))
      (node (ref "IC19") (pin "1") (pinfunction "B_1") (pintype "input"))
      (node (ref "IC22") (pin "16") (pinfunction "Y2_16") (pintype "tri_state"))
      (node (ref "IC26") (pin "1") (pinfunction "B_1") (pintype "input"))
      (node (ref "IC29") (pin "16") (pinfunction "Y2_16") (pintype "tri_state"))
      (node (ref "IC35") (pin "13") (pinfunction "B6_13") (pintype "bidirectional"))
      (node (ref "IC4") (pin "1") (pinfunction "B_1") (pintype "input"))
      (node (ref "IC7") (pin "16") (pinfunction "Y2_16") (pintype "tri_state"))
      (node (ref "RN1") (pin "7") (pinfunction "1_7") (pintype "passive"))
    )
    (net (code "52") (name "ADATA6") (class "Default")
      (node (ref "IC12") (pin "10") (pinfunction "C_10") (pintype "input"))
      (node (ref "IC15") (pin "14") (pinfunction "Y3_14") (pintype "tri_state"))
      (node (ref "IC19") (pin "10") (pinfunction "C_10") (pintype "input"))
      (node (ref "IC22") (pin "14") (pinfunction "Y3_14") (pintype "tri_state"))
      (node (ref "IC26") (pin "10") (pinfunction "C_10") (pintype "input"))
      (node (ref "IC29") (pin "14") (pinfunction "Y3_14") (pintype "tri_state"))
      (node (ref "IC35") (pin "12") (pinfunction "B7_12") (pintype "bidirectional"))
      (node (ref "IC4") (pin "10") (pinfunction "C_10") (pintype "input"))
      (node (ref "IC7") (pin "14") (pinfunction "Y3_14") (pintype "tri_state"))
      (node (ref "RN1") (pin "8") (pinfunction "1_8") (pintype "passive"))
    )
    (net (code "53") (name "ADATA7") (class "Default")
      (node (ref "IC12") (pin "9") (pinfunction "D_9") (pintype "input"))
      (node (ref "IC15") (pin "12") (pinfunction "Y4_12") (pintype "tri_state"))
      (node (ref "IC19") (pin "9") (pinfunction "D_9") (pintype "input"))
      (node (ref "IC22") (pin "12") (pinfunction "Y4_12") (pintype "tri_state"))
      (node (ref "IC26") (pin "9") (pinfunction "D_9") (pintype "input"))
      (node (ref "IC29") (pin "12") (pinfunction "Y4_12") (pintype "tri_state"))
      (node (ref "IC35") (pin "11") (pinfunction "B8_11") (pintype "bidirectional"))
      (node (ref "IC4") (pin "9") (pinfunction "D_9") (pintype "input"))
      (node (ref "IC7") (pin "12") (pinfunction "Y4_12") (pintype "tri_state"))
      (node (ref "RN1") (pin "9") (pinfunction "1_9") (pintype "passive"))
    )
    (net (code "54") (name "ADATA8") (class "Default")
      (node (ref "IC13") (pin "15") (pinfunction "A_15") (pintype "input"))
      (node (ref "IC16") (pin "9") (pinfunction "Y1_9") (pintype "tri_state"))
      (node (ref "IC20") (pin "15") (pinfunction "A_15") (pintype "input"))
      (node (ref "IC23") (pin "9") (pinfunction "Y1_9") (pintype "tri_state"))
      (node (ref "IC27") (pin "15") (pinfunction "A_15") (pintype "input"))
      (node (ref "IC30") (pin "9") (pinfunction "Y1_9") (pintype "tri_state"))
      (node (ref "IC36") (pin "18") (pinfunction "B1_18") (pintype "bidirectional"))
      (node (ref "IC37") (pin "18") (pinfunction "B1_18") (pintype "bidirectional"))
      (node (ref "IC5") (pin "15") (pinfunction "A_15") (pintype "input"))
      (node (ref "IC8") (pin "9") (pinfunction "Y1_9") (pintype "tri_state"))
      (node (ref "RN2") (pin "2") (pinfunction "1_2") (pintype "passive"))
    )
    (net (code "55") (name "ADATA9") (class "Default")
      (node (ref "IC13") (pin "1") (pinfunction "B_1") (pintype "input"))
      (node (ref "IC16") (pin "7") (pinfunction "Y2_7") (pintype "tri_state"))
      (node (ref "IC20") (pin "1") (pinfunction "B_1") (pintype "input"))
      (node (ref "IC23") (pin "7") (pinfunction "Y2_7") (pintype "tri_state"))
      (node (ref "IC27") (pin "1") (pinfunction "B_1") (pintype "input"))
      (node (ref "IC30") (pin "7") (pinfunction "Y2_7") (pintype "tri_state"))
      (node (ref "IC36") (pin "17") (pinfunction "B2_17") (pintype "bidirectional"))
      (node (ref "IC37") (pin "17") (pinfunction "B2_17") (pintype "bidirectional"))
      (node (ref "IC5") (pin "1") (pinfunction "B_1") (pintype "input"))
      (node (ref "IC8") (pin "7") (pinfunction "Y2_7") (pintype "tri_state"))
      (node (ref "RN2") (pin "3") (pinfunction "1_3") (pintype "passive"))
    )
    (net (code "56") (name "ADATA10") (class "Default")
      (node (ref "IC13") (pin "10") (pinfunction "C_10") (pintype "input"))
      (node (ref "IC16") (pin "5") (pinfunction "Y3_5") (pintype "tri_state"))
      (node (ref "IC20") (pin "10") (pinfunction "C_10") (pintype "input"))
      (node (ref "IC23") (pin "5") (pinfunction "Y3_5") (pintype "tri_state"))
      (node (ref "IC27") (pin "10") (pinfunction "C_10") (pintype "input"))
      (node (ref "IC30") (pin "5") (pinfunction "Y3_5") (pintype "tri_state"))
      (node (ref "IC36") (pin "16") (pinfunction "B3_16") (pintype "bidirectional"))
      (node (ref "IC37") (pin "16") (pinfunction "B3_16") (pintype "bidirectional"))
      (node (ref "IC5") (pin "10") (pinfunction "C_10") (pintype "input"))
      (node (ref "IC8") (pin "5") (pinfunction "Y3_5") (pintype "tri_state"))
      (node (ref "RN2") (pin "4") (pinfunction "1_4") (pintype "passive"))
    )
    (net (code "57") (name "ADATA11") (class "Default")
      (node (ref "IC13") (pin "9") (pinfunction "D_9") (pintype "input"))
      (node (ref "IC16") (pin "3") (pinfunction "Y4_3") (pintype "tri_state"))
      (node (ref "IC20") (pin "9") (pinfunction "D_9") (pintype "input"))
      (node (ref "IC23") (pin "3") (pinfunction "Y4_3") (pintype "tri_state"))
      (node (ref "IC27") (pin "9") (pinfunction "D_9") (pintype "input"))
      (node (ref "IC30") (pin "3") (pinfunction "Y4_3") (pintype "tri_state"))
      (node (ref "IC36") (pin "15") (pinfunction "B4_15") (pintype "bidirectional"))
      (node (ref "IC37") (pin "15") (pinfunction "B4_15") (pintype "bidirectional"))
      (node (ref "IC5") (pin "9") (pinfunction "D_9") (pintype "input"))
      (node (ref "IC8") (pin "3") (pinfunction "Y4_3") (pintype "tri_state"))
      (node (ref "RN2") (pin "5") (pinfunction "1_5") (pintype "passive"))
    )
    (net (code "58") (name "ADATA12") (class "Default")
      (node (ref "IC14") (pin "15") (pinfunction "A_15") (pintype "input"))
      (node (ref "IC16") (pin "18") (pinfunction "Y1_18") (pintype "tri_state"))
      (node (ref "IC21") (pin "15") (pinfunction "A_15") (pintype "input"))
      (node (ref "IC23") (pin "18") (pinfunction "Y1_18") (pintype "tri_state"))
      (node (ref "IC28") (pin "15") (pinfunction "A_15") (pintype "input"))
      (node (ref "IC30") (pin "18") (pinfunction "Y1_18") (pintype "tri_state"))
      (node (ref "IC36") (pin "14") (pinfunction "B5_14") (pintype "bidirectional"))
      (node (ref "IC37") (pin "14") (pinfunction "B5_14") (pintype "bidirectional"))
      (node (ref "IC6") (pin "15") (pinfunction "A_15") (pintype "input"))
      (node (ref "IC8") (pin "18") (pinfunction "Y1_18") (pintype "tri_state"))
      (node (ref "RN2") (pin "6") (pinfunction "1_6") (pintype "passive"))
    )
    (net (code "59") (name "ADATA13") (class "Default")
      (node (ref "IC14") (pin "1") (pinfunction "B_1") (pintype "input"))
      (node (ref "IC16") (pin "16") (pinfunction "Y2_16") (pintype "tri_state"))
      (node (ref "IC21") (pin "1") (pinfunction "B_1") (pintype "input"))
      (node (ref "IC23") (pin "16") (pinfunction "Y2_16") (pintype "tri_state"))
      (node (ref "IC28") (pin "1") (pinfunction "B_1") (pintype "input"))
      (node (ref "IC30") (pin "16") (pinfunction "Y2_16") (pintype "tri_state"))
      (node (ref "IC36") (pin "13") (pinfunction "B6_13") (pintype "bidirectional"))
      (node (ref "IC37") (pin "13") (pinfunction "B6_13") (pintype "bidirectional"))
      (node (ref "IC6") (pin "1") (pinfunction "B_1") (pintype "input"))
      (node (ref "IC8") (pin "16") (pinfunction "Y2_16") (pintype "tri_state"))
      (node (ref "RN2") (pin "7") (pinfunction "1_7") (pintype "passive"))
    )
    (net (code "60") (name "ADATA14") (class "Default")
      (node (ref "IC14") (pin "10") (pinfunction "C_10") (pintype "input"))
      (node (ref "IC16") (pin "14") (pinfunction "Y3_14") (pintype "tri_state"))
      (node (ref "IC21") (pin "10") (pinfunction "C_10") (pintype "input"))
      (node (ref "IC23") (pin "14") (pinfunction "Y3_14") (pintype "tri_state"))
      (node (ref "IC28") (pin "10") (pinfunction "C_10") (pintype "input"))
      (node (ref "IC30") (pin "14") (pinfunction "Y3_14") (pintype "tri_state"))
      (node (ref "IC36") (pin "12") (pinfunction "B7_12") (pintype "bidirectional"))
      (node (ref "IC37") (pin "12") (pinfunction "B7_12") (pintype "bidirectional"))
      (node (ref "IC6") (pin "10") (pinfunction "C_10") (pintype "input"))
      (node (ref "IC8") (pin "14") (pinfunction "Y3_14") (pintype "tri_state"))
      (node (ref "RN2") (pin "8") (pinfunction "1_8") (pintype "passive"))
    )
    (net (code "61") (name "ADATA15") (class "Default")
      (node (ref "IC14") (pin "9") (pinfunction "D_9") (pintype "input"))
      (node (ref "IC16") (pin "12") (pinfunction "Y4_12") (pintype "tri_state"))
      (node (ref "IC21") (pin "9") (pinfunction "D_9") (pintype "input"))
      (node (ref "IC23") (pin "12") (pinfunction "Y4_12") (pintype "tri_state"))
      (node (ref "IC28") (pin "9") (pinfunction "D_9") (pintype "input"))
      (node (ref "IC30") (pin "12") (pinfunction "Y4_12") (pintype "tri_state"))
      (node (ref "IC36") (pin "11") (pinfunction "B8_11") (pintype "bidirectional"))
      (node (ref "IC37") (pin "11") (pinfunction "B8_11") (pintype "bidirectional"))
      (node (ref "IC6") (pin "9") (pinfunction "D_9") (pintype "input"))
      (node (ref "IC8") (pin "12") (pinfunction "Y4_12") (pintype "tri_state"))
      (node (ref "RN2") (pin "9") (pinfunction "1_9") (pintype "passive"))
    )
    (net (code "62") (name "ADDR0") (class "Default")
      (node (ref "X1") (pin "A3") (pinfunction "B_A3") (pintype "passive"))
    )
    (net (code "63") (name "ADDR1") (class "Default")
      (node (ref "X1") (pin "A4") (pinfunction "B_A4") (pintype "passive"))
    )
    (net (code "64") (name "ADDR2") (class "Default")
      (node (ref "X1") (pin "A5") (pinfunction "B_A5") (pintype "passive"))
    )
    (net (code "65") (name "ADDR3") (class "Default")
      (node (ref "X1") (pin "A6") (pinfunction "B_A6") (pintype "passive"))
    )
    (net (code "66") (name "ADDR4") (class "Default")
      (node (ref "X1") (pin "A7") (pinfunction "B_A7") (pintype "passive"))
    )
    (net (code "67") (name "ADDR5") (class "Default")
      (node (ref "X1") (pin "A8") (pinfunction "B_A8") (pintype "passive"))
    )
    (net (code "68") (name "ADDR6") (class "Default")
      (node (ref "X1") (pin "A9") (pinfunction "B_A9") (pintype "passive"))
    )
    (net (code "69") (name "ADDR7") (class "Default")
      (node (ref "X1") (pin "A10") (pinfunction "B_A10") (pintype "passive"))
    )
    (net (code "70") (name "ADDR8") (class "Default")
      (node (ref "X1") (pin "A11") (pinfunction "B_A11") (pintype "passive"))
    )
    (net (code "71") (name "ADDR9") (class "Default")
      (node (ref "X1") (pin "A12") (pinfunction "B_A12") (pintype "passive"))
    )
    (net (code "72") (name "ADDR10") (class "Default")
      (node (ref "X1") (pin "A13") (pinfunction "B_A13") (pintype "passive"))
    )
    (net (code "73") (name "ADDR11") (class "Default")
      (node (ref "X1") (pin "A14") (pinfunction "B_A14") (pintype "passive"))
    )
    (net (code "74") (name "ADDR12") (class "Default")
      (node (ref "X1") (pin "A15") (pinfunction "B_A15") (pintype "passive"))
    )
    (net (code "75") (name "ADDR13") (class "Default")
      (node (ref "X1") (pin "A16") (pinfunction "B_A16") (pintype "passive"))
    )
    (net (code "76") (name "ADDR14") (class "Default")
      (node (ref "X1") (pin "A17") (pinfunction "B_A17") (pintype "passive"))
    )
    (net (code "77") (name "ADDR15") (class "Default")
      (node (ref "X1") (pin "A18") (pinfunction "B_A18") (pintype "passive"))
    )
    (net (code "78") (name "ALU0") (class "Default")
      (node (ref "X1") (pin "C16") (pinfunction "B_C16") (pintype "passive"))
    )
    (net (code "79") (name "ALU1") (class "Default")
      (node (ref "X1") (pin "C17") (pinfunction "B_C17") (pintype "passive"))
    )
    (net (code "80") (name "ALU2") (class "Default")
      (node (ref "X1") (pin "C18") (pinfunction "B_C18") (pintype "passive"))
    )
    (net (code "81") (name "ALU3") (class "Default")
      (node (ref "X1") (pin "C19") (pinfunction "B_C19") (pintype "passive"))
    )
    (net (code "82") (name "BR-COND") (class "Default")
      (node (ref "X1") (pin "C24") (pinfunction "B_C24") (pintype "passive"))
    )
    (net (code "83") (name "BUS-DIR") (class "Default")
      (node (ref "IC35") (pin "1") (pinfunction "DIR_1") (pintype "input"))
      (node (ref "IC36") (pin "1") (pinfunction "DIR_1") (pintype "input"))
      (node (ref "IC37") (pin "1") (pinfunction "DIR_1") (pintype "input"))
      (node (ref "IC38") (pin "3") (pinfunction "O_3") (pintype "open_collector"))
    )
    (net (code "84") (name "DATA0") (class "Default")
      (node (ref "IC35") (pin "2") (pinfunction "A1_2") (pintype "bidirectional"))
      (node (ref "IC37") (pin "2") (pinfunction "A1_2") (pintype "bidirectional"))
      (node (ref "X1") (pin "A19") (pinfunction "B_A19") (pintype "passive"))
    )
    (net (code "85") (name "DATA1") (class "Default")
      (node (ref "IC35") (pin "3") (pinfunction "A2_3") (pintype "bidirectional"))
      (node (ref "IC37") (pin "3") (pinfunction "A2_3") (pintype "bidirectional"))
      (node (ref "X1") (pin "A20") (pinfunction "B_A20") (pintype "passive"))
    )
    (net (code "86") (name "DATA2") (class "Default")
      (node (ref "IC35") (pin "4") (pinfunction "A3_4") (pintype "bidirectional"))
      (node (ref "IC37") (pin "4") (pinfunction "A3_4") (pintype "bidirectional"))
      (node (ref "X1") (pin "A21") (pinfunction "B_A21") (pintype "passive"))
    )
    (net (code "87") (name "DATA3") (class "Default")
      (node (ref "IC35") (pin "5") (pinfunction "A4_5") (pintype "bidirectional"))
      (node (ref "IC37") (pin "5") (pinfunction "A4_5") (pintype "bidirectional"))
      (node (ref "X1") (pin "A22") (pinfunction "B_A22") (pintype "passive"))
    )
    (net (code "88") (name "DATA4") (class "Default")
      (node (ref "IC35") (pin "6") (pinfunction "A5_6") (pintype "bidirectional"))
      (node (ref "IC37") (pin "6") (pinfunction "A5_6") (pintype "bidirectional"))
      (node (ref "X1") (pin "A23") (pinfunction "B_A23") (pintype "passive"))
    )
    (net (code "89") (name "DATA5") (class "Default")
      (node (ref "IC35") (pin "7") (pinfunction "A6_7") (pintype "bidirectional"))
      (node (ref "IC37") (pin "7") (pinfunction "A6_7") (pintype "bidirectional"))
      (node (ref "X1") (pin "A24") (pinfunction "B_A24") (pintype "passive"))
    )
    (net (code "90") (name "DATA6") (class "Default")
      (node (ref "IC35") (pin "8") (pinfunction "A7_8") (pintype "bidirectional"))
      (node (ref "IC37") (pin "8") (pinfunction "A7_8") (pintype "bidirectional"))
      (node (ref "X1") (pin "A25") (pinfunction "B_A25") (pintype "passive"))
    )
    (net (code "91") (name "DATA7") (class "Default")
      (node (ref "IC35") (pin "9") (pinfunction "A8_9") (pintype "bidirectional"))
      (node (ref "IC37") (pin "9") (pinfunction "A8_9") (pintype "bidirectional"))
      (node (ref "X1") (pin "A26") (pinfunction "B_A26") (pintype "passive"))
    )
    (net (code "92") (name "DATA8") (class "Default")
      (node (ref "IC36") (pin "2") (pinfunction "A1_2") (pintype "bidirectional"))
      (node (ref "X1") (pin "A27") (pinfunction "B_A27") (pintype "passive"))
    )
    (net (code "93") (name "DATA9") (class "Default")
      (node (ref "IC36") (pin "3") (pinfunction "A2_3") (pintype "bidirectional"))
      (node (ref "X1") (pin "A28") (pinfunction "B_A28") (pintype "passive"))
    )
    (net (code "94") (name "DATA10") (class "Default")
      (node (ref "IC36") (pin "4") (pinfunction "A3_4") (pintype "bidirectional"))
      (node (ref "X1") (pin "A29") (pinfunction "B_A29") (pintype "passive"))
    )
    (net (code "95") (name "DATA11") (class "Default")
      (node (ref "IC36") (pin "5") (pinfunction "A4_5") (pintype "bidirectional"))
      (node (ref "X1") (pin "A30") (pinfunction "B_A30") (pintype "passive"))
    )
    (net (code "96") (name "DATA12") (class "Default")
      (node (ref "IC36") (pin "6") (pinfunction "A5_6") (pintype "bidirectional"))
      (node (ref "X1") (pin "B3") (pinfunction "B_B3") (pintype "passive"))
    )
    (net (code "97") (name "DATA13") (class "Default")
      (node (ref "IC36") (pin "7") (pinfunction "A6_7") (pintype "bidirectional"))
      (node (ref "X1") (pin "B4") (pinfunction "B_B4") (pintype "passive"))
    )
    (net (code "98") (name "DATA14") (class "Default")
      (node (ref "IC36") (pin "8") (pinfunction "A7_8") (pintype "bidirectional"))
      (node (ref "X1") (pin "B5") (pinfunction "B_B5") (pintype "passive"))
    )
    (net (code "99") (name "DATA15") (class "Default")
      (node (ref "IC36") (pin "9") (pinfunction "A8_9") (pintype "bidirectional"))
      (node (ref "X1") (pin "B6") (pinfunction "B_B6") (pintype "passive"))
    )
    (net (code "100") (name "GND") (class "Default")
      (node (ref "C1") (pin "2") (pinfunction "2_2") (pintype "passive"))
      (node (ref "C10") (pin "2") (pinfunction "2_2") (pintype "passive"))
      (node (ref "C11") (pin "2") (pinfunction "2_2") (pintype "passive"))
      (node (ref "C12") (pin "2") (pinfunction "2_2") (pintype "passive"))
      (node (ref "C13") (pin "2") (pinfunction "2_2") (pintype "passive"))
      (node (ref "C14") (pin "2") (pinfunction "2_2") (pintype "passive"))
      (node (ref "C15") (pin "2") (pinfunction "2_2") (pintype "passive"))
      (node (ref "C16") (pin "2") (pinfunction "2_2") (pintype "passive"))
      (node (ref "C17") (pin "2") (pinfunction "2_2") (pintype "passive"))
      (node (ref "C18") (pin "2") (pinfunction "2_2") (pintype "passive"))
      (node (ref "C19") (pin "2") (pinfunction "2_2") (pintype "passive"))
      (node (ref "C2") (pin "2") (pinfunction "2_2") (pintype "passive"))
      (node (ref "C20") (pin "2") (pinfunction "2_2") (pintype "passive"))
      (node (ref "C21") (pin "2") (pinfunction "2_2") (pintype "passive"))
      (node (ref "C22") (pin "2") (pinfunction "2_2") (pintype "passive"))
      (node (ref "C23") (pin "2") (pinfunction "2_2") (pintype "passive"))
      (node (ref "C24") (pin "2") (pinfunction "2_2") (pintype "passive"))
      (node (ref "C25") (pin "2") (pinfunction "2_2") (pintype "passive"))
      (node (ref "C26") (pin "2") (pinfunction "2_2") (pintype "passive"))
      (node (ref "C27") (pin "2") (pinfunction "2_2") (pintype "passive"))
      (node (ref "C28") (pin "2") (pinfunction "2_2") (pintype "passive"))
      (node (ref "C29") (pin "2") (pinfunction "2_2") (pintype "passive"))
      (node (ref "C3") (pin "2") (pinfunction "2_2") (pintype "passive"))
      (node (ref "C30") (pin "2") (pinfunction "2_2") (pintype "passive"))
      (node (ref "C31") (pin "2") (pinfunction "2_2") (pintype "passive"))
      (node (ref "C32") (pin "2") (pinfunction "2_2") (pintype "passive"))
      (node (ref "C33") (pin "2") (pinfunction "2_2") (pintype "passive"))
      (node (ref "C34") (pin "2") (pinfunction "2_2") (pintype "passive"))
      (node (ref "C35") (pin "2") (pinfunction "2_2") (pintype "passive"))
      (node (ref "C36") (pin "2") (pinfunction "2_2") (pintype "passive"))
      (node (ref "C37") (pin "2") (pinfunction "2_2") (pintype "passive"))
      (node (ref "C38") (pin "2") (pinfunction "2_2") (pintype "passive"))
      (node (ref "C4") (pin "2") (pinfunction "2_2") (pintype "passive"))
      (node (ref "C5") (pin "2") (pinfunction "2_2") (pintype "passive"))
      (node (ref "C6") (pin "2") (pinfunction "2_2") (pintype "passive"))
      (node (ref "C8") (pin "2") (pinfunction "2_2") (pintype "passive"))
      (node (ref "C9") (pin "2") (pinfunction "2_2") (pintype "passive"))
      (node (ref "IC38") (pin "1") (pinfunction "I0_1") (pintype "input"))
      (node (ref "IC38") (pin "5") (pinfunction "I0_5") (pintype "input"))
      (node (ref "IC38") (pin "8") (pinfunction "I0_8") (pintype "input"))
      (node (ref "JP1") (pin "1") (pinfunction "1_1") (pintype "passive"))
      (node (ref "JP1") (pin "2") (pinfunction "2_2") (pintype "passive"))
      (node (ref "JP1") (pin "39") (pinfunction "39_39") (pintype "passive"))
      (node (ref "JP1") (pin "40") (pinfunction "40_40") (pintype "passive"))
      (node (ref "JP2") (pin "1") (pinfunction "1_1") (pintype "passive"))
      (node (ref "JP2") (pin "2") (pinfunction "2_2") (pintype "passive"))
      (node (ref "JP2") (pin "39") (pinfunction "39_39") (pintype "passive"))
      (node (ref "JP2") (pin "40") (pinfunction "40_40") (pintype "passive"))
      (node (ref "PWR") (pin "K") (pinfunction "C_K") (pintype "passive"))
      (node (ref "X1") (pin "A1") (pinfunction "B_A1") (pintype "passive"))
      (node (ref "X1") (pin "A32") (pinfunction "B_A32") (pintype "passive"))
      (node (ref "X1") (pin "B1") (pinfunction "B_B1") (pintype "passive"))
      (node (ref "X1") (pin "B32") (pinfunction "B_B32") (pintype "passive"))
      (node (ref "X1") (pin "C1") (pinfunction "B_C1") (pintype "passive"))
      (node (ref "X1") (pin "C32") (pinfunction "B_C32") (pintype "passive"))
    )
    (net (code "101") (name "IA-0") (class "Default")
      (node (ref "IC11") (pin "3") (pinfunction "QA_3") (pintype "output"))
      (node (ref "IC15") (pin "11") (pinfunction "A1_11") (pintype "input"))
      (node (ref "JP2") (pin "5") (pinfunction "5_5") (pintype "passive"))
    )
    (net (code "102") (name "IA-1") (class "Default")
      (node (ref "IC11") (pin "2") (pinfunction "QB_2") (pintype "output"))
      (node (ref "IC15") (pin "13") (pinfunction "A2_13") (pintype "input"))
      (node (ref "JP2") (pin "7") (pinfunction "7_7") (pintype "passive"))
    )
    (net (code "103") (name "IA-2") (class "Default")
      (node (ref "IC11") (pin "6") (pinfunction "QC_6") (pintype "output"))
      (node (ref "IC15") (pin "15") (pinfunction "A3_15") (pintype "input"))
      (node (ref "JP2") (pin "9") (pinfunction "9_9") (pintype "passive"))
    )
    (net (code "104") (name "IA-3") (class "Default")
      (node (ref "IC11") (pin "7") (pinfunction "QD_7") (pintype "output"))
      (node (ref "IC15") (pin "17") (pinfunction "A4_17") (pintype "input"))
      (node (ref "JP2") (pin "11") (pinfunction "11_11") (pintype "passive"))
    )
    (net (code "105") (name "IA-4") (class "Default")
      (node (ref "IC12") (pin "3") (pinfunction "QA_3") (pintype "output"))
      (node (ref "IC15") (pin "2") (pinfunction "A1_2") (pintype "input"))
      (node (ref "JP2") (pin "13") (pinfunction "13_13") (pintype "passive"))
    )
    (net (code "106") (name "IA-5") (class "Default")
      (node (ref "IC12") (pin "2") (pinfunction "QB_2") (pintype "output"))
      (node (ref "IC15") (pin "4") (pinfunction "A2_4") (pintype "input"))
      (node (ref "JP2") (pin "15") (pinfunction "15_15") (pintype "passive"))
    )
    (net (code "107") (name "IA-6") (class "Default")
      (node (ref "IC12") (pin "6") (pinfunction "QC_6") (pintype "output"))
      (node (ref "IC15") (pin "6") (pinfunction "A3_6") (pintype "input"))
      (node (ref "JP2") (pin "17") (pinfunction "17_17") (pintype "passive"))
    )
    (net (code "108") (name "IA-7") (class "Default")
      (node (ref "IC12") (pin "7") (pinfunction "QD_7") (pintype "output"))
      (node (ref "IC15") (pin "8") (pinfunction "A4_8") (pintype "input"))
      (node (ref "JP2") (pin "19") (pinfunction "19_19") (pintype "passive"))
    )
    (net (code "109") (name "IA-8") (class "Default")
      (node (ref "IC13") (pin "3") (pinfunction "QA_3") (pintype "output"))
      (node (ref "IC16") (pin "11") (pinfunction "A1_11") (pintype "input"))
      (node (ref "JP2") (pin "21") (pinfunction "21_21") (pintype "passive"))
    )
    (net (code "110") (name "IA-9") (class "Default")
      (node (ref "IC13") (pin "2") (pinfunction "QB_2") (pintype "output"))
      (node (ref "IC16") (pin "13") (pinfunction "A2_13") (pintype "input"))
      (node (ref "JP2") (pin "23") (pinfunction "23_23") (pintype "passive"))
    )
    (net (code "111") (name "IA-10") (class "Default")
      (node (ref "IC13") (pin "6") (pinfunction "QC_6") (pintype "output"))
      (node (ref "IC16") (pin "15") (pinfunction "A3_15") (pintype "input"))
      (node (ref "JP2") (pin "25") (pinfunction "25_25") (pintype "passive"))
    )
    (net (code "112") (name "IA-11") (class "Default")
      (node (ref "IC13") (pin "7") (pinfunction "QD_7") (pintype "output"))
      (node (ref "IC16") (pin "17") (pinfunction "A4_17") (pintype "input"))
      (node (ref "JP2") (pin "27") (pinfunction "27_27") (pintype "passive"))
    )
    (net (code "113") (name "IA-12") (class "Default")
      (node (ref "IC14") (pin "3") (pinfunction "QA_3") (pintype "output"))
      (node (ref "IC16") (pin "2") (pinfunction "A1_2") (pintype "input"))
      (node (ref "JP2") (pin "29") (pinfunction "29_29") (pintype "passive"))
    )
    (net (code "114") (name "IA-13") (class "Default")
      (node (ref "IC14") (pin "2") (pinfunction "QB_2") (pintype "output"))
      (node (ref "IC16") (pin "4") (pinfunction "A2_4") (pintype "input"))
      (node (ref "JP2") (pin "31") (pinfunction "31_31") (pintype "passive"))
    )
    (net (code "115") (name "IA-14") (class "Default")
      (node (ref "IC14") (pin "6") (pinfunction "QC_6") (pintype "output"))
      (node (ref "IC16") (pin "6") (pinfunction "A3_6") (pintype "input"))
      (node (ref "JP2") (pin "33") (pinfunction "33_33") (pintype "passive"))
    )
    (net (code "116") (name "IA-15") (class "Default")
      (node (ref "IC14") (pin "7") (pinfunction "QD_7") (pintype "output"))
      (node (ref "IC16") (pin "8") (pinfunction "A4_8") (pintype "input"))
      (node (ref "JP2") (pin "35") (pinfunction "35_35") (pintype "passive"))
    )
    (net (code "117") (name "IB-0") (class "Default")
      (node (ref "JP2") (pin "6") (pinfunction "6_6") (pintype "passive"))
    )
    (net (code "118") (name "IB-1") (class "Default")
      (node (ref "JP2") (pin "8") (pinfunction "8_8") (pintype "passive"))
    )
    (net (code "119") (name "IB-2") (class "Default")
      (node (ref "JP2") (pin "10") (pinfunction "10_10") (pintype "passive"))
    )
    (net (code "120") (name "IB-3") (class "Default")
      (node (ref "JP2") (pin "12") (pinfunction "12_12") (pintype "passive"))
    )
    (net (code "121") (name "IB-4") (class "Default")
      (node (ref "JP2") (pin "14") (pinfunction "14_14") (pintype "passive"))
    )
    (net (code "122") (name "IB-5") (class "Default")
      (node (ref "JP2") (pin "16") (pinfunction "16_16") (pintype "passive"))
    )
    (net (code "123") (name "IB-6") (class "Default")
      (node (ref "JP2") (pin "18") (pinfunction "18_18") (pintype "passive"))
    )
    (net (code "124") (name "IB-7") (class "Default")
      (node (ref "JP2") (pin "20") (pinfunction "20_20") (pintype "passive"))
    )
    (net (code "125") (name "IB-8") (class "Default")
      (node (ref "JP2") (pin "22") (pinfunction "22_22") (pintype "passive"))
    )
    (net (code "126") (name "IB-9") (class "Default")
      (node (ref "JP2") (pin "24") (pinfunction "24_24") (pintype "passive"))
    )
    (net (code "127") (name "IB-10") (class "Default")
      (node (ref "JP2") (pin "26") (pinfunction "26_26") (pintype "passive"))
    )
    (net (code "128") (name "IB-11") (class "Default")
      (node (ref "JP2") (pin "28") (pinfunction "28_28") (pintype "passive"))
    )
    (net (code "129") (name "IB-12") (class "Default")
      (node (ref "JP2") (pin "30") (pinfunction "30_30") (pintype "passive"))
    )
    (net (code "130") (name "IB-13") (class "Default")
      (node (ref "JP2") (pin "32") (pinfunction "32_32") (pintype "passive"))
    )
    (net (code "131") (name "IB-14") (class "Default")
      (node (ref "JP2") (pin "34") (pinfunction "34_34") (pintype "passive"))
    )
    (net (code "132") (name "IB-15") (class "Default")
      (node (ref "JP2") (pin "36") (pinfunction "36_36") (pintype "passive"))
    )
    (net (code "133") (name "IC-0") (class "Default")
      (node (ref "IC25") (pin "3") (pinfunction "QA_3") (pintype "output"))
      (node (ref "IC29") (pin "11") (pinfunction "A1_11") (pintype "input"))
      (node (ref "JP1") (pin "5") (pinfunction "5_5") (pintype "passive"))
    )
    (net (code "134") (name "IC-1") (class "Default")
      (node (ref "IC25") (pin "2") (pinfunction "QB_2") (pintype "output"))
      (node (ref "IC29") (pin "13") (pinfunction "A2_13") (pintype "input"))
      (node (ref "JP1") (pin "7") (pinfunction "7_7") (pintype "passive"))
    )
    (net (code "135") (name "IC-2") (class "Default")
      (node (ref "IC25") (pin "6") (pinfunction "QC_6") (pintype "output"))
      (node (ref "IC29") (pin "15") (pinfunction "A3_15") (pintype "input"))
      (node (ref "JP1") (pin "9") (pinfunction "9_9") (pintype "passive"))
    )
    (net (code "136") (name "IC-3") (class "Default")
      (node (ref "IC25") (pin "7") (pinfunction "QD_7") (pintype "output"))
      (node (ref "IC29") (pin "17") (pinfunction "A4_17") (pintype "input"))
      (node (ref "JP1") (pin "11") (pinfunction "11_11") (pintype "passive"))
    )
    (net (code "137") (name "IC-4") (class "Default")
      (node (ref "IC26") (pin "3") (pinfunction "QA_3") (pintype "output"))
      (node (ref "IC29") (pin "2") (pinfunction "A1_2") (pintype "input"))
      (node (ref "JP1") (pin "13") (pinfunction "13_13") (pintype "passive"))
    )
    (net (code "138") (name "IC-5") (class "Default")
      (node (ref "IC26") (pin "2") (pinfunction "QB_2") (pintype "output"))
      (node (ref "IC29") (pin "4") (pinfunction "A2_4") (pintype "input"))
      (node (ref "JP1") (pin "15") (pinfunction "15_15") (pintype "passive"))
    )
    (net (code "139") (name "IC-6") (class "Default")
      (node (ref "IC26") (pin "6") (pinfunction "QC_6") (pintype "output"))
      (node (ref "IC29") (pin "6") (pinfunction "A3_6") (pintype "input"))
      (node (ref "JP1") (pin "17") (pinfunction "17_17") (pintype "passive"))
    )
    (net (code "140") (name "IC-7") (class "Default")
      (node (ref "IC26") (pin "7") (pinfunction "QD_7") (pintype "output"))
      (node (ref "IC29") (pin "8") (pinfunction "A4_8") (pintype "input"))
      (node (ref "JP1") (pin "19") (pinfunction "19_19") (pintype "passive"))
    )
    (net (code "141") (name "IC-8") (class "Default")
      (node (ref "IC27") (pin "3") (pinfunction "QA_3") (pintype "output"))
      (node (ref "IC30") (pin "11") (pinfunction "A1_11") (pintype "input"))
      (node (ref "JP1") (pin "21") (pinfunction "21_21") (pintype "passive"))
    )
    (net (code "142") (name "IC-9") (class "Default")
      (node (ref "IC27") (pin "2") (pinfunction "QB_2") (pintype "output"))
      (node (ref "IC30") (pin "13") (pinfunction "A2_13") (pintype "input"))
      (node (ref "JP1") (pin "23") (pinfunction "23_23") (pintype "passive"))
    )
    (net (code "143") (name "IC-10") (class "Default")
      (node (ref "IC27") (pin "6") (pinfunction "QC_6") (pintype "output"))
      (node (ref "IC30") (pin "15") (pinfunction "A3_15") (pintype "input"))
      (node (ref "JP1") (pin "25") (pinfunction "25_25") (pintype "passive"))
    )
    (net (code "144") (name "IC-11") (class "Default")
      (node (ref "IC27") (pin "7") (pinfunction "QD_7") (pintype "output"))
      (node (ref "IC30") (pin "17") (pinfunction "A4_17") (pintype "input"))
      (node (ref "JP1") (pin "27") (pinfunction "27_27") (pintype "passive"))
    )
    (net (code "145") (name "IC-12") (class "Default")
      (node (ref "IC28") (pin "3") (pinfunction "QA_3") (pintype "output"))
      (node (ref "IC30") (pin "2") (pinfunction "A1_2") (pintype "input"))
    )
    (net (code "146") (name "IC-13") (class "Default")
      (node (ref "IC28") (pin "2") (pinfunction "QB_2") (pintype "output"))
      (node (ref "IC30") (pin "4") (pinfunction "A2_4") (pintype "input"))
      (node (ref "JP1") (pin "31") (pinfunction "31_31") (pintype "passive"))
    )
    (net (code "147") (name "IC-14") (class "Default")
      (node (ref "IC28") (pin "6") (pinfunction "QC_6") (pintype "output"))
      (node (ref "IC30") (pin "6") (pinfunction "A3_6") (pintype "input"))
      (node (ref "JP1") (pin "33") (pinfunction "33_33") (pintype "passive"))
    )
    (net (code "148") (name "IC-15") (class "Default")
      (node (ref "IC28") (pin "7") (pinfunction "QD_7") (pintype "output"))
      (node (ref "IC30") (pin "8") (pinfunction "A4_8") (pintype "input"))
      (node (ref "JP1") (pin "35") (pinfunction "35_35") (pintype "passive"))
    )
    (net (code "149") (name "ID-0") (class "Default")
      (node (ref "JP1") (pin "6") (pinfunction "6_6") (pintype "passive"))
    )
    (net (code "150") (name "ID-1") (class "Default")
      (node (ref "JP1") (pin "8") (pinfunction "8_8") (pintype "passive"))
    )
    (net (code "151") (name "ID-2") (class "Default")
      (node (ref "JP1") (pin "10") (pinfunction "10_10") (pintype "passive"))
    )
    (net (code "152") (name "ID-3") (class "Default")
      (node (ref "JP1") (pin "12") (pinfunction "12_12") (pintype "passive"))
    )
    (net (code "153") (name "ID-4") (class "Default")
      (node (ref "JP1") (pin "14") (pinfunction "14_14") (pintype "passive"))
    )
    (net (code "154") (name "ID-5") (class "Default")
      (node (ref "JP1") (pin "16") (pinfunction "16_16") (pintype "passive"))
    )
    (net (code "155") (name "ID-6") (class "Default")
      (node (ref "JP1") (pin "18") (pinfunction "18_18") (pintype "passive"))
    )
    (net (code "156") (name "ID-7") (class "Default")
      (node (ref "JP1") (pin "20") (pinfunction "20_20") (pintype "passive"))
    )
    (net (code "157") (name "ID-8") (class "Default")
      (node (ref "JP1") (pin "22") (pinfunction "22_22") (pintype "passive"))
    )
    (net (code "158") (name "ID-9") (class "Default")
      (node (ref "JP1") (pin "24") (pinfunction "24_24") (pintype "passive"))
    )
    (net (code "159") (name "ID-10") (class "Default")
      (node (ref "JP1") (pin "26") (pinfunction "26_26") (pintype "passive"))
    )
    (net (code "160") (name "ID-11") (class "Default")
      (node (ref "JP1") (pin "28") (pinfunction "28_28") (pintype "passive"))
    )
    (net (code "161") (name "ID-12") (class "Default")
      (node (ref "JP1") (pin "30") (pinfunction "30_30") (pintype "passive"))
    )
    (net (code "162") (name "ID-13") (class "Default")
      (node (ref "JP1") (pin "32") (pinfunction "32_32") (pintype "passive"))
    )
    (net (code "163") (name "ID-14") (class "Default")
      (node (ref "JP1") (pin "34") (pinfunction "34_34") (pintype "passive"))
    )
    (net (code "164") (name "ID-15") (class "Default")
      (node (ref "JP1") (pin "36") (pinfunction "36_36") (pintype "passive"))
    )
    (net (code "165") (name "IN") (class "Default")
      (node (ref "X1") (pin "C26") (pinfunction "B_C26") (pintype "passive"))
    )
    (net (code "166") (name "IO-ADDR0") (class "Default")
      (node (ref "X1") (pin "C7") (pinfunction "B_C7") (pintype "passive"))
    )
    (net (code "167") (name "IO-ADDR1") (class "Default")
      (node (ref "X1") (pin "C8") (pinfunction "B_C8") (pintype "passive"))
    )
    (net (code "168") (name "IO-ADDR2") (class "Default")
      (node (ref "X1") (pin "C9") (pinfunction "B_C9") (pintype "passive"))
    )
    (net (code "169") (name "IO-ADDR3") (class "Default")
      (node (ref "X1") (pin "C10") (pinfunction "B_C10") (pintype "passive"))
    )
    (net (code "170") (name "Net-(IC1A-O)") (class "Default")
      (node (ref "IC1") (pin "3") (pinfunction "O_3") (pintype "output"))
      (node (ref "IC3") (pin "5") (pinfunction "UP_5") (pintype "input"))
    )
    (net (code "171") (name "Net-(IC1B-O)") (class "Default")
      (node (ref "IC1") (pin "6") (pinfunction "O_6") (pintype "output"))
      (node (ref "IC3") (pin "4") (pinfunction "DN_4") (pintype "input"))
    )
    (net (code "172") (name "Net-(IC1C-O)") (class "Default")
      (node (ref "IC1") (pin "8") (pinfunction "O_8") (pintype "output"))
      (node (ref "IC3") (pin "11") (pinfunction "LD_11") (pintype "input"))
      (node (ref "IC4") (pin "11") (pinfunction "LD_11") (pintype "input"))
    )
    (net (code "173") (name "Net-(IC1D-O)") (class "Default")
      (node (ref "IC1") (pin "11") (pinfunction "O_11") (pintype "output"))
      (node (ref "IC5") (pin "11") (pinfunction "LD_11") (pintype "input"))
      (node (ref "IC6") (pin "11") (pinfunction "LD_11") (pintype "input"))
    )
    (net (code "174") (name "Net-(IC2A-O)") (class "Default")
      (node (ref "IC2") (pin "3") (pinfunction "O_3") (pintype "output"))
      (node (ref "IC7") (pin "1") (pinfunction "G_1") (pintype "input"))
      (node (ref "IC7") (pin "19") (pinfunction "G_19") (pintype "input"))
    )
    (net (code "175") (name "Net-(IC2B-O)") (class "Default")
      (node (ref "IC2") (pin "6") (pinfunction "O_6") (pintype "output"))
      (node (ref "IC8") (pin "1") (pinfunction "G_1") (pintype "input"))
      (node (ref "IC8") (pin "19") (pinfunction "G_19") (pintype "input"))
    )
    (net (code "176") (name "Net-(IC3A-BO)") (class "Default")
      (node (ref "IC3") (pin "13") (pinfunction "BO_13") (pintype "output"))
      (node (ref "IC4") (pin "4") (pinfunction "DN_4") (pintype "input"))
    )
    (net (code "177") (name "Net-(IC3A-CO)") (class "Default")
      (node (ref "IC3") (pin "12") (pinfunction "CO_12") (pintype "output"))
      (node (ref "IC4") (pin "5") (pinfunction "UP_5") (pintype "input"))
    )
    (net (code "178") (name "Net-(IC3A-QA)") (class "Default")
      (node (ref "IC3") (pin "3") (pinfunction "QA_3") (pintype "output"))
      (node (ref "IC7") (pin "11") (pinfunction "A1_11") (pintype "input"))
    )
    (net (code "179") (name "Net-(IC3A-QB)") (class "Default")
      (node (ref "IC3") (pin "2") (pinfunction "QB_2") (pintype "output"))
      (node (ref "IC7") (pin "13") (pinfunction "A2_13") (pintype "input"))
    )
    (net (code "180") (name "Net-(IC3A-QC)") (class "Default")
      (node (ref "IC3") (pin "6") (pinfunction "QC_6") (pintype "output"))
      (node (ref "IC7") (pin "15") (pinfunction "A3_15") (pintype "input"))
    )
    (net (code "181") (name "Net-(IC3A-QD)") (class "Default")
      (node (ref "IC3") (pin "7") (pinfunction "QD_7") (pintype "output"))
      (node (ref "IC7") (pin "17") (pinfunction "A4_17") (pintype "input"))
    )
    (net (code "182") (name "Net-(IC4A-BO)") (class "Default")
      (node (ref "IC4") (pin "13") (pinfunction "BO_13") (pintype "output"))
      (node (ref "IC5") (pin "4") (pinfunction "DN_4") (pintype "input"))
    )
    (net (code "183") (name "Net-(IC4A-CO)") (class "Default")
      (node (ref "IC4") (pin "12") (pinfunction "CO_12") (pintype "output"))
      (node (ref "IC5") (pin "5") (pinfunction "UP_5") (pintype "input"))
    )
    (net (code "184") (name "Net-(IC4A-QA)") (class "Default")
      (node (ref "IC4") (pin "3") (pinfunction "QA_3") (pintype "output"))
      (node (ref "IC7") (pin "2") (pinfunction "A1_2") (pintype "input"))
    )
    (net (code "185") (name "Net-(IC4A-QB)") (class "Default")
      (node (ref "IC4") (pin "2") (pinfunction "QB_2") (pintype "output"))
      (node (ref "IC7") (pin "4") (pinfunction "A2_4") (pintype "input"))
    )
    (net (code "186") (name "Net-(IC4A-QC)") (class "Default")
      (node (ref "IC4") (pin "6") (pinfunction "QC_6") (pintype "output"))
      (node (ref "IC7") (pin "6") (pinfunction "A3_6") (pintype "input"))
    )
    (net (code "187") (name "Net-(IC4A-QD)") (class "Default")
      (node (ref "IC4") (pin "7") (pinfunction "QD_7") (pintype "output"))
      (node (ref "IC7") (pin "8") (pinfunction "A4_8") (pintype "input"))
    )
    (net (code "188") (name "Net-(IC5A-BO)") (class "Default")
      (node (ref "IC5") (pin "13") (pinfunction "BO_13") (pintype "output"))
      (node (ref "IC6") (pin "4") (pinfunction "DN_4") (pintype "input"))
    )
    (net (code "189") (name "Net-(IC5A-CO)") (class "Default")
      (node (ref "IC5") (pin "12") (pinfunction "CO_12") (pintype "output"))
      (node (ref "IC6") (pin "5") (pinfunction "UP_5") (pintype "input"))
    )
    (net (code "190") (name "Net-(IC5A-QA)") (class "Default")
      (node (ref "IC5") (pin "3") (pinfunction "QA_3") (pintype "output"))
      (node (ref "IC8") (pin "11") (pinfunction "A1_11") (pintype "input"))
    )
    (net (code "191") (name "Net-(IC5A-QB)") (class "Default")
      (node (ref "IC5") (pin "2") (pinfunction "QB_2") (pintype "output"))
      (node (ref "IC8") (pin "13") (pinfunction "A2_13") (pintype "input"))
    )
    (net (code "192") (name "Net-(IC5A-QC)") (class "Default")
      (node (ref "IC5") (pin "6") (pinfunction "QC_6") (pintype "output"))
      (node (ref "IC8") (pin "15") (pinfunction "A3_15") (pintype "input"))
    )
    (net (code "193") (name "Net-(IC5A-QD)") (class "Default")
      (node (ref "IC5") (pin "7") (pinfunction "QD_7") (pintype "output"))
      (node (ref "IC8") (pin "17") (pinfunction "A4_17") (pintype "input"))
    )
    (net (code "194") (name "Net-(IC6A-QA)") (class "Default")
      (node (ref "IC6") (pin "3") (pinfunction "QA_3") (pintype "output"))
      (node (ref "IC8") (pin "2") (pinfunction "A1_2") (pintype "input"))
    )
    (net (code "195") (name "Net-(IC6A-QB)") (class "Default")
      (node (ref "IC6") (pin "2") (pinfunction "QB_2") (pintype "output"))
      (node (ref "IC8") (pin "4") (pinfunction "A2_4") (pintype "input"))
    )
    (net (code "196") (name "Net-(IC6A-QC)") (class "Default")
      (node (ref "IC6") (pin "6") (pinfunction "QC_6") (pintype "output"))
      (node (ref "IC8") (pin "6") (pinfunction "A3_6") (pintype "input"))
    )
    (net (code "197") (name "Net-(IC6A-QD)") (class "Default")
      (node (ref "IC6") (pin "7") (pinfunction "QD_7") (pintype "output"))
      (node (ref "IC8") (pin "8") (pinfunction "A4_8") (pintype "input"))
    )
    (net (code "198") (name "Net-(IC10A-O)") (class "Default")
      (node (ref "IC10") (pin "3") (pinfunction "O_3") (pintype "output"))
      (node (ref "IC15") (pin "1") (pinfunction "G_1") (pintype "input"))
      (node (ref "IC15") (pin "19") (pinfunction "G_19") (pintype "input"))
    )
    (net (code "199") (name "Net-(IC10B-O)") (class "Default")
      (node (ref "IC10") (pin "6") (pinfunction "O_6") (pintype "output"))
      (node (ref "IC16") (pin "1") (pinfunction "G_1") (pintype "input"))
      (node (ref "IC16") (pin "19") (pinfunction "G_19") (pintype "input"))
    )
    (net (code "200") (name "Net-(IC10C-O)") (class "Default")
      (node (ref "IC10") (pin "8") (pinfunction "O_8") (pintype "output"))
      (node (ref "IC29") (pin "1") (pinfunction "G_1") (pintype "input"))
      (node (ref "IC29") (pin "19") (pinfunction "G_19") (pintype "input"))
    )
    (net (code "201") (name "Net-(IC10D-O)") (class "Default")
      (node (ref "IC10") (pin "11") (pinfunction "O_11") (pintype "output"))
      (node (ref "IC30") (pin "1") (pinfunction "G_1") (pintype "input"))
      (node (ref "IC30") (pin "19") (pinfunction "G_19") (pintype "input"))
    )
    (net (code "202") (name "Net-(IC11A-BO)") (class "Default")
      (node (ref "IC11") (pin "13") (pinfunction "BO_13") (pintype "output"))
      (node (ref "IC12") (pin "4") (pinfunction "DN_4") (pintype "input"))
    )
    (net (code "203") (name "Net-(IC11A-CO)") (class "Default")
      (node (ref "IC11") (pin "12") (pinfunction "CO_12") (pintype "output"))
      (node (ref "IC12") (pin "5") (pinfunction "UP_5") (pintype "input"))
    )
    (net (code "204") (name "Net-(IC11A-DN)") (class "Default")
      (node (ref "IC11") (pin "4") (pinfunction "DN_4") (pintype "input"))
      (node (ref "IC9") (pin "6") (pinfunction "O_6") (pintype "output"))
    )
    (net (code "205") (name "Net-(IC11A-LD)") (class "Default")
      (node (ref "IC11") (pin "11") (pinfunction "LD_11") (pintype "input"))
      (node (ref "IC12") (pin "11") (pinfunction "LD_11") (pintype "input"))
      (node (ref "IC9") (pin "8") (pinfunction "O_8") (pintype "output"))
    )
    (net (code "206") (name "Net-(IC11A-UP)") (class "Default")
      (node (ref "IC11") (pin "5") (pinfunction "UP_5") (pintype "input"))
      (node (ref "IC9") (pin "3") (pinfunction "O_3") (pintype "output"))
    )
    (net (code "207") (name "Net-(IC12A-BO)") (class "Default")
      (node (ref "IC12") (pin "13") (pinfunction "BO_13") (pintype "output"))
      (node (ref "IC13") (pin "4") (pinfunction "DN_4") (pintype "input"))
    )
    (net (code "208") (name "Net-(IC12A-CO)") (class "Default")
      (node (ref "IC12") (pin "12") (pinfunction "CO_12") (pintype "output"))
      (node (ref "IC13") (pin "5") (pinfunction "UP_5") (pintype "input"))
    )
    (net (code "209") (name "Net-(IC13A-BO)") (class "Default")
      (node (ref "IC13") (pin "13") (pinfunction "BO_13") (pintype "output"))
      (node (ref "IC14") (pin "4") (pinfunction "DN_4") (pintype "input"))
    )
    (net (code "210") (name "Net-(IC13A-CO)") (class "Default")
      (node (ref "IC13") (pin "12") (pinfunction "CO_12") (pintype "output"))
      (node (ref "IC14") (pin "5") (pinfunction "UP_5") (pintype "input"))
    )
    (net (code "211") (name "Net-(IC13A-LD)") (class "Default")
      (node (ref "IC13") (pin "11") (pinfunction "LD_11") (pintype "input"))
      (node (ref "IC14") (pin "11") (pinfunction "LD_11") (pintype "input"))
      (node (ref "IC9") (pin "11") (pinfunction "O_11") (pintype "output"))
    )
    (net (code "212") (name "Net-(IC17A-O)") (class "Default")
      (node (ref "IC17") (pin "3") (pinfunction "O_3") (pintype "output"))
      (node (ref "IC18") (pin "5") (pinfunction "UP_5") (pintype "input"))
    )
    (net (code "213") (name "Net-(IC17B-O)") (class "Default")
      (node (ref "IC17") (pin "6") (pinfunction "O_6") (pintype "output"))
      (node (ref "IC18") (pin "4") (pinfunction "DN_4") (pintype "input"))
    )
    (net (code "214") (name "Net-(IC17C-O)") (class "Default")
      (node (ref "IC17") (pin "8") (pinfunction "O_8") (pintype "output"))
      (node (ref "IC18") (pin "11") (pinfunction "LD_11") (pintype "input"))
      (node (ref "IC19") (pin "11") (pinfunction "LD_11") (pintype "input"))
    )
    (net (code "215") (name "Net-(IC17D-O)") (class "Default")
      (node (ref "IC17") (pin "11") (pinfunction "O_11") (pintype "output"))
      (node (ref "IC20") (pin "11") (pinfunction "LD_11") (pintype "input"))
      (node (ref "IC21") (pin "11") (pinfunction "LD_11") (pintype "input"))
    )
    (net (code "216") (name "Net-(IC18A-BO)") (class "Default")
      (node (ref "IC18") (pin "13") (pinfunction "BO_13") (pintype "output"))
      (node (ref "IC19") (pin "4") (pinfunction "DN_4") (pintype "input"))
    )
    (net (code "217") (name "Net-(IC18A-CO)") (class "Default")
      (node (ref "IC18") (pin "12") (pinfunction "CO_12") (pintype "output"))
      (node (ref "IC19") (pin "5") (pinfunction "UP_5") (pintype "input"))
    )
    (net (code "218") (name "Net-(IC18A-QA)") (class "Default")
      (node (ref "IC18") (pin "3") (pinfunction "QA_3") (pintype "output"))
      (node (ref "IC22") (pin "11") (pinfunction "A1_11") (pintype "input"))
    )
    (net (code "219") (name "Net-(IC18A-QB)") (class "Default")
      (node (ref "IC18") (pin "2") (pinfunction "QB_2") (pintype "output"))
      (node (ref "IC22") (pin "13") (pinfunction "A2_13") (pintype "input"))
    )
    (net (code "220") (name "Net-(IC18A-QC)") (class "Default")
      (node (ref "IC18") (pin "6") (pinfunction "QC_6") (pintype "output"))
      (node (ref "IC22") (pin "15") (pinfunction "A3_15") (pintype "input"))
    )
    (net (code "221") (name "Net-(IC18A-QD)") (class "Default")
      (node (ref "IC18") (pin "7") (pinfunction "QD_7") (pintype "output"))
      (node (ref "IC22") (pin "17") (pinfunction "A4_17") (pintype "input"))
    )
    (net (code "222") (name "Net-(IC19A-BO)") (class "Default")
      (node (ref "IC19") (pin "13") (pinfunction "BO_13") (pintype "output"))
      (node (ref "IC20") (pin "4") (pinfunction "DN_4") (pintype "input"))
    )
    (net (code "223") (name "Net-(IC19A-CO)") (class "Default")
      (node (ref "IC19") (pin "12") (pinfunction "CO_12") (pintype "output"))
      (node (ref "IC20") (pin "5") (pinfunction "UP_5") (pintype "input"))
    )
    (net (code "224") (name "Net-(IC19A-QA)") (class "Default")
      (node (ref "IC19") (pin "3") (pinfunction "QA_3") (pintype "output"))
      (node (ref "IC22") (pin "2") (pinfunction "A1_2") (pintype "input"))
    )
    (net (code "225") (name "Net-(IC19A-QB)") (class "Default")
      (node (ref "IC19") (pin "2") (pinfunction "QB_2") (pintype "output"))
      (node (ref "IC22") (pin "4") (pinfunction "A2_4") (pintype "input"))
    )
    (net (code "226") (name "Net-(IC19A-QC)") (class "Default")
      (node (ref "IC19") (pin "6") (pinfunction "QC_6") (pintype "output"))
      (node (ref "IC22") (pin "6") (pinfunction "A3_6") (pintype "input"))
    )
    (net (code "227") (name "Net-(IC19A-QD)") (class "Default")
      (node (ref "IC19") (pin "7") (pinfunction "QD_7") (pintype "output"))
      (node (ref "IC22") (pin "8") (pinfunction "A4_8") (pintype "input"))
    )
    (net (code "228") (name "Net-(IC20A-BO)") (class "Default")
      (node (ref "IC20") (pin "13") (pinfunction "BO_13") (pintype "output"))
      (node (ref "IC21") (pin "4") (pinfunction "DN_4") (pintype "input"))
    )
    (net (code "229") (name "Net-(IC20A-CO)") (class "Default")
      (node (ref "IC20") (pin "12") (pinfunction "CO_12") (pintype "output"))
      (node (ref "IC21") (pin "5") (pinfunction "UP_5") (pintype "input"))
    )
    (net (code "230") (name "Net-(IC20A-QA)") (class "Default")
      (node (ref "IC20") (pin "3") (pinfunction "QA_3") (pintype "output"))
      (node (ref "IC23") (pin "11") (pinfunction "A1_11") (pintype "input"))
    )
    (net (code "231") (name "Net-(IC20A-QB)") (class "Default")
      (node (ref "IC20") (pin "2") (pinfunction "QB_2") (pintype "output"))
      (node (ref "IC23") (pin "13") (pinfunction "A2_13") (pintype "input"))
    )
    (net (code "232") (name "Net-(IC20A-QC)") (class "Default")
      (node (ref "IC20") (pin "6") (pinfunction "QC_6") (pintype "output"))
      (node (ref "IC23") (pin "15") (pinfunction "A3_15") (pintype "input"))
    )
    (net (code "233") (name "Net-(IC20A-QD)") (class "Default")
      (node (ref "IC20") (pin "7") (pinfunction "QD_7") (pintype "output"))
      (node (ref "IC23") (pin "17") (pinfunction "A4_17") (pintype "input"))
    )
    (net (code "234") (name "Net-(IC21A-QA)") (class "Default")
      (node (ref "IC21") (pin "3") (pinfunction "QA_3") (pintype "output"))
      (node (ref "IC23") (pin "2") (pinfunction "A1_2") (pintype "input"))
    )
    (net (code "235") (name "Net-(IC21A-QB)") (class "Default")
      (node (ref "IC21") (pin "2") (pinfunction "QB_2") (pintype "output"))
      (node (ref "IC23") (pin "4") (pinfunction "A2_4") (pintype "input"))
    )
    (net (code "236") (name "Net-(IC21A-QC)") (class "Default")
      (node (ref "IC21") (pin "6") (pinfunction "QC_6") (pintype "output"))
      (node (ref "IC23") (pin "6") (pinfunction "A3_6") (pintype "input"))
    )
    (net (code "237") (name "Net-(IC21A-QD)") (class "Default")
      (node (ref "IC21") (pin "7") (pinfunction "QD_7") (pintype "output"))
      (node (ref "IC23") (pin "8") (pinfunction "A4_8") (pintype "input"))
    )
    (net (code "238") (name "Net-(IC22A-G)") (class "Default")
      (node (ref "IC2") (pin "8") (pinfunction "O_8") (pintype "output"))
      (node (ref "IC22") (pin "1") (pinfunction "G_1") (pintype "input"))
      (node (ref "IC22") (pin "19") (pinfunction "G_19") (pintype "input"))
    )
    (net (code "239") (name "Net-(IC23A-G)") (class "Default")
      (node (ref "IC2") (pin "11") (pinfunction "O_11") (pintype "output"))
      (node (ref "IC23") (pin "1") (pinfunction "G_1") (pintype "input"))
      (node (ref "IC23") (pin "19") (pinfunction "G_19") (pintype "input"))
    )
    (net (code "240") (name "Net-(IC24A-O)") (class "Default")
      (node (ref "IC24") (pin "3") (pinfunction "O_3") (pintype "output"))
      (node (ref "IC25") (pin "5") (pinfunction "UP_5") (pintype "input"))
    )
    (net (code "241") (name "Net-(IC24B-O)") (class "Default")
      (node (ref "IC24") (pin "6") (pinfunction "O_6") (pintype "output"))
      (node (ref "IC25") (pin "4") (pinfunction "DN_4") (pintype "input"))
    )
    (net (code "242") (name "Net-(IC24C-O)") (class "Default")
      (node (ref "IC24") (pin "8") (pinfunction "O_8") (pintype "output"))
      (node (ref "IC25") (pin "11") (pinfunction "LD_11") (pintype "input"))
      (node (ref "IC26") (pin "11") (pinfunction "LD_11") (pintype "input"))
    )
    (net (code "243") (name "Net-(IC24D-O)") (class "Default")
      (node (ref "IC24") (pin "11") (pinfunction "O_11") (pintype "output"))
      (node (ref "IC27") (pin "11") (pinfunction "LD_11") (pintype "input"))
      (node (ref "IC28") (pin "11") (pinfunction "LD_11") (pintype "input"))
    )
    (net (code "244") (name "Net-(IC25A-BO)") (class "Default")
      (node (ref "IC25") (pin "13") (pinfunction "BO_13") (pintype "output"))
      (node (ref "IC26") (pin "4") (pinfunction "DN_4") (pintype "input"))
    )
    (net (code "245") (name "Net-(IC25A-CO)") (class "Default")
      (node (ref "IC25") (pin "12") (pinfunction "CO_12") (pintype "output"))
      (node (ref "IC26") (pin "5") (pinfunction "UP_5") (pintype "input"))
    )
    (net (code "246") (name "Net-(IC26A-BO)") (class "Default")
      (node (ref "IC26") (pin "13") (pinfunction "BO_13") (pintype "output"))
      (node (ref "IC27") (pin "4") (pinfunction "DN_4") (pintype "input"))
    )
    (net (code "247") (name "Net-(IC26A-CO)") (class "Default")
      (node (ref "IC26") (pin "12") (pinfunction "CO_12") (pintype "output"))
      (node (ref "IC27") (pin "5") (pinfunction "UP_5") (pintype "input"))
    )
    (net (code "248") (name "Net-(IC27A-BO)") (class "Default")
      (node (ref "IC27") (pin "13") (pinfunction "BO_13") (pintype "output"))
      (node (ref "IC28") (pin "4") (pinfunction "DN_4") (pintype "input"))
    )
    (net (code "249") (name "Net-(IC27A-CO)") (class "Default")
      (node (ref "IC27") (pin "12") (pinfunction "CO_12") (pintype "output"))
      (node (ref "IC28") (pin "5") (pinfunction "UP_5") (pintype "input"))
    )
    (net (code "250") (name "Net-(IC31A-O)") (class "Default")
      (node (ref "IC31") (pin "3") (pinfunction "O_3") (pintype "output"))
      (node (ref "IC32") (pin "1") (pinfunction "G_1") (pintype "input"))
    )
    (net (code "251") (name "Net-(IC31B-O)") (class "Default")
      (node (ref "IC31") (pin "6") (pinfunction "O_6") (pintype "output"))
      (node (ref "IC32") (pin "15") (pinfunction "G_15") (pintype "input"))
    )
    (net (code "252") (name "Net-(IC31C-I0)") (class "Default")
      (node (ref "IC31") (pin "9") (pinfunction "I0_9") (pintype "input"))
      (node (ref "IC38") (pin "4") (pinfunction "O_4") (pintype "open_collector"))
    )
    (net (code "253") (name "Net-(IC31C-I1)") (class "Default")
      (node (ref "IC31") (pin "10") (pinfunction "I1_10") (pintype "input"))
      (node (ref "IC31") (pin "12") (pinfunction "I0_12") (pintype "input"))
      (node (ref "IC38") (pin "11") (pinfunction "O_11") (pintype "open_collector"))
    )
    (net (code "254") (name "Net-(IC31C-O)") (class "Default")
      (node (ref "IC31") (pin "8") (pinfunction "O_8") (pintype "output"))
      (node (ref "IC35") (pin "19") (pinfunction "G_19") (pintype "input"))
      (node (ref "IC36") (pin "19") (pinfunction "G_19") (pintype "input"))
    )
    (net (code "255") (name "Net-(IC31D-O)") (class "Default")
      (node (ref "IC31") (pin "11") (pinfunction "O_11") (pintype "output"))
      (node (ref "IC37") (pin "19") (pinfunction "G_19") (pintype "input"))
    )
    (net (code "256") (name "Net-(IC32A-Y1)") (class "Default")
      (node (ref "IC32") (pin "5") (pinfunction "Y1_5") (pintype "output"))
      (node (ref "J1") (pin "3") (pinfunction "3_3") (pintype "passive"))
    )
    (net (code "257") (name "Net-(IC32A-Y2)") (class "Default")
      (node (ref "IC32") (pin "6") (pinfunction "Y2_6") (pintype "output"))
      (node (ref "J1") (pin "5") (pinfunction "5_5") (pintype "passive"))
    )
    (net (code "258") (name "Net-(IC32A-Y3)") (class "Default")
      (node (ref "IC32") (pin "7") (pinfunction "Y3_7") (pintype "output"))
      (node (ref "J1") (pin "7") (pinfunction "7_7") (pintype "passive"))
    )
    (net (code "259") (name "Net-(IC32B-Y1)") (class "Default")
      (node (ref "IC32") (pin "11") (pinfunction "Y1_11") (pintype "output"))
      (node (ref "J2") (pin "3") (pinfunction "3_3") (pintype "passive"))
    )
    (net (code "260") (name "Net-(IC32B-Y2)") (class "Default")
      (node (ref "IC32") (pin "10") (pinfunction "Y2_10") (pintype "output"))
      (node (ref "J2") (pin "5") (pinfunction "5_5") (pintype "passive"))
    )
    (net (code "261") (name "Net-(IC32B-Y3)") (class "Default")
      (node (ref "IC32") (pin "9") (pinfunction "Y3_9") (pintype "output"))
      (node (ref "J2") (pin "7") (pinfunction "7_7") (pintype "passive"))
    )
    (net (code "262") (name "Net-(PWR-PadA)") (class "Default")
      (node (ref "PWR") (pin "A") (pinfunction "A_A") (pintype "passive"))
      (node (ref "R1") (pin "1") (pinfunction "1_1") (pintype "passive"))
    )
    (net (code "263") (name "OUT") (class "Default")
      (node (ref "X1") (pin "C27") (pinfunction "B_C27") (pintype "passive"))
    )
    (net (code "264") (name "REG-LD-ID0") (class "Default")
      (node (ref "IC33") (pin "14") (pinfunction "A_14") (pintype "input"))
      (node (ref "X1") (pin "B13") (pinfunction "B_B13") (pintype "passive"))
    )
    (net (code "265") (name "REG-LD-ID1") (class "Default")
      (node (ref "IC33") (pin "13") (pinfunction "B_13") (pintype "input"))
      (node (ref "X1") (pin "B14") (pinfunction "B_B14") (pintype "passive"))
    )
    (net (code "266") (name "REG-LD-ID2") (class "Default")
      (node (ref "IC32") (pin "14") (pinfunction "A_14") (pintype "input"))
      (node (ref "X1") (pin "B15") (pinfunction "B_B15") (pintype "passive"))
    )
    (net (code "267") (name "REG-LD-ID3") (class "Default")
      (node (ref "IC32") (pin "13") (pinfunction "B_13") (pintype "input"))
      (node (ref "X1") (pin "B16") (pinfunction "B_B16") (pintype "passive"))
    )
    (net (code "268") (name "REG-RD-ID0") (class "Default")
      (node (ref "IC33") (pin "2") (pinfunction "A_2") (pintype "input"))
      (node (ref "X1") (pin "B9") (pinfunction "B_B9") (pintype "passive"))
    )
    (net (code "269") (name "REG-RD-ID1") (class "Default")
      (node (ref "IC33") (pin "3") (pinfunction "B_3") (pintype "input"))
      (node (ref "X1") (pin "B10") (pinfunction "B_B10") (pintype "passive"))
    )
    (net (code "270") (name "REG-RD-ID2") (class "Default")
      (node (ref "IC32") (pin "2") (pinfunction "A_2") (pintype "input"))
      (node (ref "X1") (pin "B11") (pinfunction "B_B11") (pintype "passive"))
    )
    (net (code "271") (name "REG-RD-ID3") (class "Default")
      (node (ref "IC32") (pin "3") (pinfunction "B_3") (pintype "input"))
      (node (ref "X1") (pin "B12") (pinfunction "B_B12") (pintype "passive"))
    )
    (net (code "272") (name "RESET") (class "Default")
      (node (ref "IC11") (pin "14") (pinfunction "CLR_14") (pintype "input"))
      (node (ref "IC12") (pin "14") (pinfunction "CLR_14") (pintype "input"))
      (node (ref "IC13") (pin "14") (pinfunction "CLR_14") (pintype "input"))
      (node (ref "IC14") (pin "14") (pinfunction "CLR_14") (pintype "input"))
      (node (ref "IC18") (pin "14") (pinfunction "CLR_14") (pintype "input"))
      (node (ref "IC19") (pin "14") (pinfunction "CLR_14") (pintype "input"))
      (node (ref "IC20") (pin "14") (pinfunction "CLR_14") (pintype "input"))
      (node (ref "IC21") (pin "14") (pinfunction "CLR_14") (pintype "input"))
      (node (ref "IC25") (pin "14") (pinfunction "CLR_14") (pintype "input"))
      (node (ref "IC26") (pin "14") (pinfunction "CLR_14") (pintype "input"))
      (node (ref "IC27") (pin "14") (pinfunction "CLR_14") (pintype "input"))
      (node (ref "IC28") (pin "14") (pinfunction "CLR_14") (pintype "input"))
      (node (ref "IC3") (pin "14") (pinfunction "CLR_14") (pintype "input"))
      (node (ref "IC38") (pin "10") (pinfunction "O_10") (pintype "open_collector"))
      (node (ref "IC4") (pin "14") (pinfunction "CLR_14") (pintype "input"))
      (node (ref "IC5") (pin "14") (pinfunction "CLR_14") (pintype "input"))
      (node (ref "IC6") (pin "14") (pinfunction "CLR_14") (pintype "input"))
    )
    (net (code "273") (name "UNUSED0") (class "Default")
      (node (ref "X1") (pin "C12") (pinfunction "B_C12") (pintype "passive"))
    )
    (net (code "274") (name "VCC") (class "Default")
      (node (ref "C1") (pin "1") (pinfunction "1_1") (pintype "passive"))
      (node (ref "C10") (pin "1") (pinfunction "1_1") (pintype "passive"))
      (node (ref "C11") (pin "1") (pinfunction "1_1") (pintype "passive"))
      (node (ref "C12") (pin "1") (pinfunction "1_1") (pintype "passive"))
      (node (ref "C13") (pin "1") (pinfunction "1_1") (pintype "passive"))
      (node (ref "C14") (pin "1") (pinfunction "1_1") (pintype "passive"))
      (node (ref "C15") (pin "1") (pinfunction "1_1") (pintype "passive"))
      (node (ref "C16") (pin "1") (pinfunction "1_1") (pintype "passive"))
      (node (ref "C17") (pin "1") (pinfunction "1_1") (pintype "passive"))
      (node (ref "C18") (pin "1") (pinfunction "1_1") (pintype "passive"))
      (node (ref "C19") (pin "1") (pinfunction "1_1") (pintype "passive"))
      (node (ref "C2") (pin "1") (pinfunction "1_1") (pintype "passive"))
      (node (ref "C20") (pin "1") (pinfunction "1_1") (pintype "passive"))
      (node (ref "C21") (pin "1") (pinfunction "1_1") (pintype "passive"))
      (node (ref "C22") (pin "1") (pinfunction "1_1") (pintype "passive"))
      (node (ref "C23") (pin "1") (pinfunction "1_1") (pintype "passive"))
      (node (ref "C24") (pin "1") (pinfunction "1_1") (pintype "passive"))
      (node (ref "C25") (pin "1") (pinfunction "1_1") (pintype "passive"))
      (node (ref "C26") (pin "1") (pinfunction "1_1") (pintype "passive"))
      (node (ref "C27") (pin "1") (pinfunction "1_1") (pintype "passive"))
      (node (ref "C28") (pin "1") (pinfunction "1_1") (pintype "passive"))
      (node (ref "C29") (pin "1") (pinfunction "1_1") (pintype "passive"))
      (node (ref "C3") (pin "1") (pinfunction "1_1") (pintype "passive"))
      (node (ref "C30") (pin "1") (pinfunction "1_1") (pintype "passive"))
      (node (ref "C31") (pin "1") (pinfunction "1_1") (pintype "passive"))
      (node (ref "C32") (pin "1") (pinfunction "1_1") (pintype "passive"))
      (node (ref "C33") (pin "1") (pinfunction "1_1") (pintype "passive"))
      (node (ref "C34") (pin "1") (pinfunction "1_1") (pintype "passive"))
      (node (ref "C35") (pin "1") (pinfunction "1_1") (pintype "passive"))
      (node (ref "C36") (pin "1") (pinfunction "1_1") (pintype "passive"))
      (node (ref "C37") (pin "1") (pinfunction "1_1") (pintype "passive"))
      (node (ref "C38") (pin "1") (pinfunction "1_1") (pintype "passive"))
      (node (ref "C4") (pin "1") (pinfunction "1_1") (pintype "passive"))
      (node (ref "C5") (pin "1") (pinfunction "1_1") (pintype "passive"))
      (node (ref "C6") (pin "1") (pinfunction "1_1") (pintype "passive"))
      (node (ref "C8") (pin "1") (pinfunction "1_1") (pintype "passive"))
      (node (ref "C9") (pin "1") (pinfunction "1_1") (pintype "passive"))
      (node (ref "R1") (pin "2") (pinfunction "2_2") (pintype "passive"))
      (node (ref "RN1") (pin "1") (pinfunction "1_1") (pintype "passive"))
      (node (ref "RN2") (pin "1") (pinfunction "1_1") (pintype "passive"))
      (node (ref "X1") (pin "A2") (pinfunction "B_A2") (pintype "passive"))
      (node (ref "X1") (pin "A31") (pinfunction "B_A31") (pintype "passive"))
      (node (ref "X1") (pin "B2") (pinfunction "B_B2") (pintype "passive"))
      (node (ref "X1") (pin "B31") (pinfunction "B_B31") (pintype "passive"))
      (node (ref "X1") (pin "C2") (pinfunction "B_C2") (pintype "passive"))
      (node (ref "X1") (pin "C31") (pinfunction "B_C31") (pintype "passive"))
    )
    (net (code "275") (name "unconnected-(IC6A-BO-Pad13)") (class "Default")
      (node (ref "IC6") (pin "13") (pinfunction "BO_13") (pintype "output"))
    )
    (net (code "276") (name "unconnected-(IC6A-CO-Pad12)") (class "Default")
      (node (ref "IC6") (pin "12") (pinfunction "CO_12") (pintype "output"))
    )
    (net (code "277") (name "unconnected-(IC14A-BO-Pad13)") (class "Default")
      (node (ref "IC14") (pin "13") (pinfunction "BO_13") (pintype "output"))
    )
    (net (code "278") (name "unconnected-(IC14A-CO-Pad12)") (class "Default")
      (node (ref "IC14") (pin "12") (pinfunction "CO_12") (pintype "output"))
    )
    (net (code "279") (name "unconnected-(IC21A-BO-Pad13)") (class "Default")
      (node (ref "IC21") (pin "13") (pinfunction "BO_13") (pintype "output"))
    )
    (net (code "280") (name "unconnected-(IC21A-CO-Pad12)") (class "Default")
      (node (ref "IC21") (pin "12") (pinfunction "CO_12") (pintype "output"))
    )
    (net (code "281") (name "unconnected-(IC28A-BO-Pad13)") (class "Default")
      (node (ref "IC28") (pin "13") (pinfunction "BO_13") (pintype "output"))
    )
    (net (code "282") (name "unconnected-(IC28A-CO-Pad12)") (class "Default")
      (node (ref "IC28") (pin "12") (pinfunction "CO_12") (pintype "output"))
    )
    (net (code "283") (name "unconnected-(JP1-Pad3)") (class "Default")
      (node (ref "JP1") (pin "3") (pinfunction "3_3") (pintype "passive"))
    )
    (net (code "284") (name "unconnected-(JP1-Pad4)") (class "Default")
      (node (ref "JP1") (pin "4") (pinfunction "4_4") (pintype "passive"))
    )
    (net (code "285") (name "unconnected-(JP1-Pad37)") (class "Default")
      (node (ref "JP1") (pin "37") (pinfunction "37_37") (pintype "passive"))
    )
    (net (code "286") (name "unconnected-(JP1-Pad38)") (class "Default")
      (node (ref "JP1") (pin "38") (pinfunction "38_38") (pintype "passive"))
    )
    (net (code "287") (name "unconnected-(JP2-Pad3)") (class "Default")
      (node (ref "JP2") (pin "3") (pinfunction "3_3") (pintype "passive"))
    )
    (net (code "288") (name "unconnected-(JP2-Pad4)") (class "Default")
      (node (ref "JP2") (pin "4") (pinfunction "4_4") (pintype "passive"))
    )
    (net (code "289") (name "unconnected-(JP2-Pad37)") (class "Default")
      (node (ref "JP2") (pin "37") (pinfunction "37_37") (pintype "passive"))
    )
    (net (code "290") (name "unconnected-(JP2-Pad38)") (class "Default")
      (node (ref "JP2") (pin "38") (pinfunction "38_38") (pintype "passive"))
    )
  )
)
